# sika_UI.net
KiCad netlist of a schematic drawn in Altium Designer
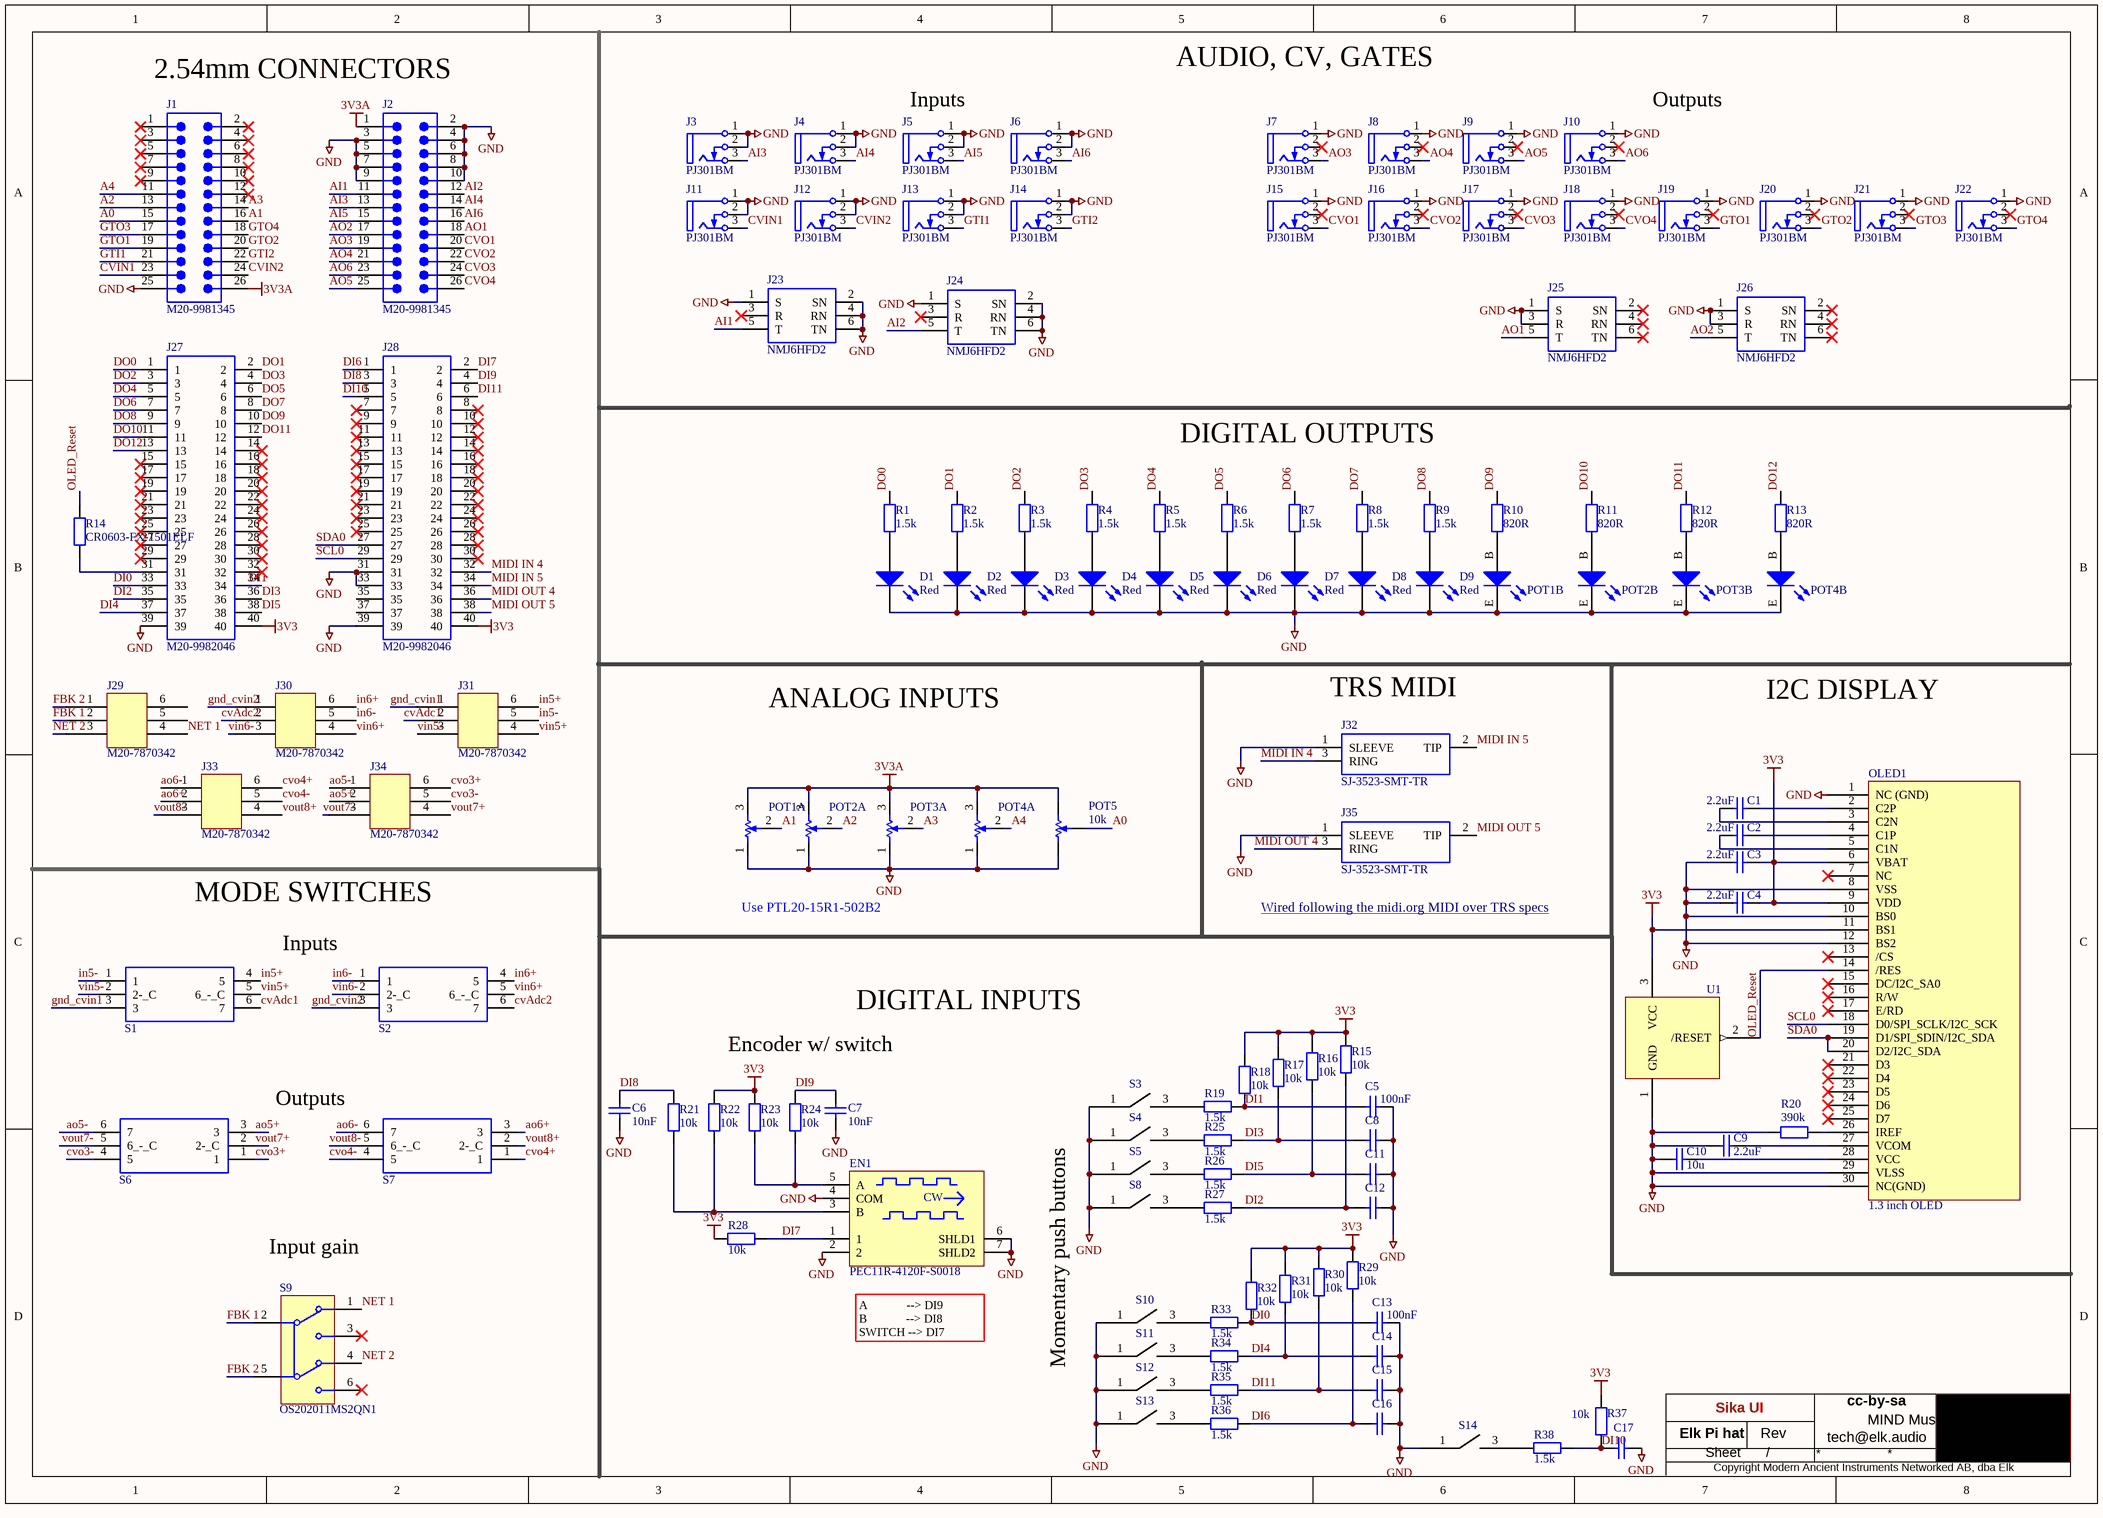
[diagram p0: sika_UI.SchDoc]

(export (version "E")
  (design (tool "Eeschema 10.0.6"))
  (components
    (comp (ref "C1")
      (value "CL10B225KP8NNNC")
      (footprint "C0603")
      (description "Cap Ceramic 10%")
      (fields
        (field (name "MANUFACTURER") "Samsung")
        (field (name "TOLERANCE") "10%")
        (field (name "CAPACITANCE") "2.2uF")
      )
      (libsource (lib "sika_UI") (part "CAP_2U2"))
    )
    (comp (ref "C2")
      (value "CL10B225KP8NNNC")
      (footprint "C0603")
      (description "Cap Ceramic 10%")
      (fields
        (field (name "MANUFACTURER") "Samsung")
        (field (name "TOLERANCE") "10%")
        (field (name "CAPACITANCE") "2.2uF")
      )
      (libsource (lib "sika_UI") (part "CAP_2U2"))
    )
    (comp (ref "C3")
      (value "CL10B225KP8NNNC")
      (footprint "C0603")
      (description "Cap Ceramic 10%")
      (fields
        (field (name "MANUFACTURER") "Samsung")
        (field (name "TOLERANCE") "10%")
        (field (name "CAPACITANCE") "2.2uF")
      )
      (libsource (lib "sika_UI") (part "CAP_2U2"))
    )
    (comp (ref "C4")
      (value "CL10B225KP8NNNC")
      (footprint "C0603")
      (description "Cap Ceramic 10%")
      (fields
        (field (name "MANUFACTURER") "Samsung")
        (field (name "TOLERANCE") "10%")
        (field (name "CAPACITANCE") "2.2uF")
      )
      (libsource (lib "sika_UI") (part "CAP_2U2"))
    )
    (comp (ref "C5")
      (value "CL10B104KO8NNNC")
      (footprint "C0603")
      (description "Cap Ceramic 10%")
      (fields
        (field (name "MANUFACTURER") "Samsung")
        (field (name "MANUFACTURER PART NUMBER") "CL10B105KO8NNNC")
        (field (name "CAPACITANCE") "100nF")
      )
      (libsource (lib "sika_UI") (part "CAP_100N"))
    )
    (comp (ref "C6")
      (value "CL10b103JB8NNNC")
      (footprint "C0603")
      (description "Cap Ceramic 10%")
      (fields
        (field (name "MANUFACTURER") "Samsung")
        (field (name "MANUFACTURER PART NUMBER") "CL10B105KO8NNNC")
        (field (name "CAPACITANCE") "10nF")
      )
      (libsource (lib "sika_UI") (part "CAP_10N"))
    )
    (comp (ref "C7")
      (value "CL10b103JB8NNNC")
      (footprint "C0603")
      (description "Cap Ceramic 10%")
      (fields
        (field (name "MANUFACTURER") "Samsung")
        (field (name "MANUFACTURER PART NUMBER") "CL10B105KO8NNNC")
        (field (name "CAPACITANCE") "10nF")
      )
      (libsource (lib "sika_UI") (part "CAP_10N"))
    )
    (comp (ref "C8")
      (value "CL10B104KO8NNNC")
      (footprint "C0603")
      (description "Cap Ceramic 10%")
      (fields
        (field (name "MANUFACTURER") "Samsung")
        (field (name "MANUFACTURER PART NUMBER") "CL10B105KO8NNNC")
      )
      (libsource (lib "sika_UI") (part "CAP_100N"))
    )
    (comp (ref "C9")
      (value "CL10B225KP8NNNC")
      (footprint "C0603")
      (description "Cap Ceramic 10%")
      (fields
        (field (name "MANUFACTURER") "Samsung")
        (field (name "TOLERANCE") "10%")
        (field (name "CAPACITANCE") "2.2uF")
      )
      (libsource (lib "sika_UI") (part "CAP_2U2"))
    )
    (comp (ref "C10")
      (value "CAP_10U")
      (footprint "C0603")
      (description "Cap Ceramic 10%")
      (fields
        (field (name "MANUFACTURER") "Samsung")
        (field (name "TOLERANCE") "10%")
        (field (name "CAPACITANCE") "10u")
      )
      (libsource (lib "sika_UI") (part "CAP_10U"))
    )
    (comp (ref "C11")
      (value "CL10B104KO8NNNC")
      (footprint "C0603")
      (description "Cap Ceramic 10%")
      (fields
        (field (name "MANUFACTURER") "Samsung")
        (field (name "MANUFACTURER PART NUMBER") "CL10B105KO8NNNC")
      )
      (libsource (lib "sika_UI") (part "CAP_100N"))
    )
    (comp (ref "C12")
      (value "CL10B104KO8NNNC")
      (footprint "C0603")
      (description "Cap Ceramic 10%")
      (fields
        (field (name "MANUFACTURER") "Samsung")
        (field (name "MANUFACTURER PART NUMBER") "CL10B105KO8NNNC")
      )
      (libsource (lib "sika_UI") (part "CAP_100N"))
    )
    (comp (ref "C13")
      (value "CL10B104KO8NNNC")
      (footprint "C0603")
      (description "Cap Ceramic 10%")
      (fields
        (field (name "MANUFACTURER") "Samsung")
        (field (name "MANUFACTURER PART NUMBER") "CL10B105KO8NNNC")
        (field (name "CAPACITANCE") "100nF")
      )
      (libsource (lib "sika_UI") (part "CAP_100N"))
    )
    (comp (ref "C14")
      (value "CL10B104KO8NNNC")
      (footprint "C0603")
      (description "Cap Ceramic 10%")
      (fields
        (field (name "MANUFACTURER") "Samsung")
        (field (name "MANUFACTURER PART NUMBER") "CL10B105KO8NNNC")
      )
      (libsource (lib "sika_UI") (part "CAP_100N"))
    )
    (comp (ref "C15")
      (value "CL10B104KO8NNNC")
      (footprint "C0603")
      (description "Cap Ceramic 10%")
      (fields
        (field (name "MANUFACTURER") "Samsung")
        (field (name "MANUFACTURER PART NUMBER") "CL10B105KO8NNNC")
      )
      (libsource (lib "sika_UI") (part "CAP_100N"))
    )
    (comp (ref "C16")
      (value "CL10B104KO8NNNC")
      (footprint "C0603")
      (description "Cap Ceramic 10%")
      (fields
        (field (name "MANUFACTURER") "Samsung")
        (field (name "MANUFACTURER PART NUMBER") "CL10B105KO8NNNC")
      )
      (libsource (lib "sika_UI") (part "CAP_100N"))
    )
    (comp (ref "C17")
      (value "CL10B104KO8NNNC")
      (footprint "C0603")
      (description "Cap Ceramic 10%")
      (fields
        (field (name "MANUFACTURER") "Samsung")
        (field (name "MANUFACTURER PART NUMBER") "CL10B105KO8NNNC")
      )
      (libsource (lib "sika_UI") (part "CAP_100N"))
    )
    (comp (ref "D1")
      (value "0")
      (footprint "PCB-9pb35s7134wdnkutz46f-1")
      (description "Standard LEDs; SMD 0610 Dome Lens LED; 1.6x0.8 mm; Red; (Cut Reel)")
      (fields (field (name "MANUFACTURER PART NUMBER") "APTD1608LSURCK") (field (name "COLOR") "Red"))
      (libsource (lib "sika_UI") (part "CMP-3990f44d6d24e657-1"))
    )
    (comp (ref "D2")
      (value "0")
      (footprint "PCB-9pb35s7134wdnkutz46f-1")
      (description "Standard LEDs; SMD 0610 Dome Lens LED; 1.6x0.8 mm; Red; (Cut Reel)")
      (fields (field (name "MANUFACTURER PART NUMBER") "APTD1608LSURCK") (field (name "COLOR") "Red"))
      (libsource (lib "sika_UI") (part "CMP-3990f44d6d24e657-1"))
    )
    (comp (ref "D3")
      (value "0")
      (footprint "PCB-9pb35s7134wdnkutz46f-1")
      (description "Standard LEDs; SMD 0610 Dome Lens LED; 1.6x0.8 mm; Red; (Cut Reel)")
      (fields (field (name "MANUFACTURER PART NUMBER") "APTD1608LSURCK") (field (name "COLOR") "Red"))
      (libsource (lib "sika_UI") (part "CMP-3990f44d6d24e657-1"))
    )
    (comp (ref "D4")
      (value "0")
      (footprint "PCB-9pb35s7134wdnkutz46f-1")
      (description "Standard LEDs; SMD 0610 Dome Lens LED; 1.6x0.8 mm; Red; (Cut Reel)")
      (fields (field (name "MANUFACTURER PART NUMBER") "APTD1608LSURCK") (field (name "COLOR") "Red"))
      (libsource (lib "sika_UI") (part "CMP-3990f44d6d24e657-1"))
    )
    (comp (ref "D5")
      (value "0")
      (footprint "PCB-9pb35s7134wdnkutz46f-1")
      (description "Standard LEDs; SMD 0610 Dome Lens LED; 1.6x0.8 mm; Red; (Cut Reel)")
      (fields (field (name "MANUFACTURER PART NUMBER") "APTD1608LSURCK") (field (name "COLOR") "Red"))
      (libsource (lib "sika_UI") (part "CMP-3990f44d6d24e657-1"))
    )
    (comp (ref "D6")
      (value "0")
      (footprint "PCB-9pb35s7134wdnkutz46f-1")
      (description "Standard LEDs; SMD 0610 Dome Lens LED; 1.6x0.8 mm; Red; (Cut Reel)")
      (fields (field (name "MANUFACTURER PART NUMBER") "APTD1608LSURCK") (field (name "COLOR") "Red"))
      (libsource (lib "sika_UI") (part "CMP-3990f44d6d24e657-1"))
    )
    (comp (ref "D7")
      (value "0")
      (footprint "PCB-9pb35s7134wdnkutz46f-1")
      (description "Standard LEDs; SMD 0610 Dome Lens LED; 1.6x0.8 mm; Red; (Cut Reel)")
      (fields (field (name "MANUFACTURER PART NUMBER") "APTD1608LSURCK") (field (name "COLOR") "Red"))
      (libsource (lib "sika_UI") (part "CMP-3990f44d6d24e657-1"))
    )
    (comp (ref "D8")
      (value "0")
      (footprint "PCB-9pb35s7134wdnkutz46f-1")
      (description "Standard LEDs; SMD 0610 Dome Lens LED; 1.6x0.8 mm; Red; (Cut Reel)")
      (fields (field (name "MANUFACTURER PART NUMBER") "APTD1608LSURCK") (field (name "COLOR") "Red"))
      (libsource (lib "sika_UI") (part "CMP-3990f44d6d24e657-1"))
    )
    (comp (ref "D9")
      (value "0")
      (footprint "PCB-9pb35s7134wdnkutz46f-1")
      (description "Standard LEDs; SMD 0610 Dome Lens LED; 1.6x0.8 mm; Red; (Cut Reel)")
      (fields (field (name "MANUFACTURER PART NUMBER") "APTD1608LSURCK") (field (name "COLOR") "Red"))
      (libsource (lib "sika_UI") (part "CMP-3990f44d6d24e657-1"))
    )
    (comp (ref "EN1")
      (value "PEC11R-4120F-S0018")
      (footprint "BOUR-PEC11R-4XXXF-SXXXX_V - Cloned")
      (description "Encoders 20mm SHAFT w/SWITCH")
      (fields (field (name "MANUFACTURER") "Bourns"))
      (libsource (lib "sika_UI") (part "PEC11R-4120F-S0018"))
    )
    (comp (ref "J1")
      (value "M20-9981345")
      (footprint "HEADER_26")
      (description "CONN HEADER 26POS .100 STR 15AU")
      (fields
        (field (name "MANUFACTURER") "Amphenol FCI")
        (field (name "MANUFACTURER PART NUMBER") "67997-226HLF")
      )
      (libsource (lib "sika_UI") (part "HEADER_26"))
    )
    (comp (ref "J2")
      (value "M20-9981345")
      (footprint "HEADER_26")
      (description "CONN HEADER 26POS .100 STR 15AU")
      (fields
        (field (name "MANUFACTURER") "Amphenol FCI")
        (field (name "MANUFACTURER PART NUMBER") "67997-226HLF")
      )
      (libsource (lib "sika_UI") (part "HEADER_26"))
    )
    (comp (ref "J3") (value "PJ301BM") (footprint "PJ301BM") (libsource (lib "sika_UI") (part "PJ301BM")))
    (comp (ref "J4") (value "PJ301BM") (footprint "PJ301BM") (libsource (lib "sika_UI") (part "PJ301BM")))
    (comp (ref "J5") (value "PJ301BM") (footprint "PJ301BM") (libsource (lib "sika_UI") (part "PJ301BM")))
    (comp (ref "J6") (value "PJ301BM") (footprint "PJ301BM") (libsource (lib "sika_UI") (part "PJ301BM")))
    (comp (ref "J7") (value "PJ301BM") (footprint "PJ301BM") (libsource (lib "sika_UI") (part "PJ301BM")))
    (comp (ref "J8") (value "PJ301BM") (footprint "PJ301BM") (libsource (lib "sika_UI") (part "PJ301BM")))
    (comp (ref "J9") (value "PJ301BM") (footprint "PJ301BM") (libsource (lib "sika_UI") (part "PJ301BM")))
    (comp (ref "J10") (value "PJ301BM") (footprint "PJ301BM") (libsource (lib "sika_UI") (part "PJ301BM")))
    (comp (ref "J11") (value "PJ301BM") (footprint "PJ301BM") (libsource (lib "sika_UI") (part "PJ301BM")))
    (comp (ref "J12") (value "PJ301BM") (footprint "PJ301BM") (libsource (lib "sika_UI") (part "PJ301BM")))
    (comp (ref "J13") (value "PJ301BM") (footprint "PJ301BM") (libsource (lib "sika_UI") (part "PJ301BM")))
    (comp (ref "J14") (value "PJ301BM") (footprint "PJ301BM") (libsource (lib "sika_UI") (part "PJ301BM")))
    (comp (ref "J15") (value "PJ301BM") (footprint "PJ301BM") (libsource (lib "sika_UI") (part "PJ301BM")))
    (comp (ref "J16") (value "PJ301BM") (footprint "PJ301BM") (libsource (lib "sika_UI") (part "PJ301BM")))
    (comp (ref "J17") (value "PJ301BM") (footprint "PJ301BM") (libsource (lib "sika_UI") (part "PJ301BM")))
    (comp (ref "J18") (value "PJ301BM") (footprint "PJ301BM") (libsource (lib "sika_UI") (part "PJ301BM")))
    (comp (ref "J19") (value "PJ301BM") (footprint "PJ301BM") (libsource (lib "sika_UI") (part "PJ301BM")))
    (comp (ref "J20") (value "PJ301BM") (footprint "PJ301BM") (libsource (lib "sika_UI") (part "PJ301BM")))
    (comp (ref "J21") (value "PJ301BM") (footprint "PJ301BM") (libsource (lib "sika_UI") (part "PJ301BM")))
    (comp (ref "J22") (value "PJ301BM") (footprint "PJ301BM") (libsource (lib "sika_UI") (part "PJ301BM")))
    (comp (ref "J23")
      (value "NMJ6HFD2")
      (footprint "NMJ6HFD2")
      (description "Phone Connectors 3C STEREO 3-SPST NC")
      (fields (field (name "MOUSER PART NUMBER") "550-20301"))
      (libsource (lib "sika_UI") (part "NMJ6HFD2"))
    )
    (comp (ref "J24")
      (value "NMJ6HFD2")
      (footprint "NMJ6HFD2")
      (description "Phone Connectors 3C STEREO 3-SPST NC")
      (fields (field (name "MOUSER PART NUMBER") "550-20301"))
      (libsource (lib "sika_UI") (part "NMJ6HFD2"))
    )
    (comp (ref "J25")
      (value "NMJ6HFD2")
      (footprint "NMJ6HFD2")
      (description "Phone Connectors 3C STEREO 3-SPST NC")
      (fields (field (name "MOUSER PART NUMBER") "550-20301"))
      (libsource (lib "sika_UI") (part "NMJ6HFD2"))
    )
    (comp (ref "J26")
      (value "NMJ6HFD2")
      (footprint "NMJ6HFD2")
      (description "Phone Connectors 3C STEREO 3-SPST NC")
      (fields (field (name "MOUSER PART NUMBER") "550-20301"))
      (libsource (lib "sika_UI") (part "NMJ6HFD2"))
    )
    (comp (ref "J27")
      (value "M20-9982046")
      (footprint "header2x20")
      (description "Unshrouded, Pitch 2.54 mm, 6.1 mm Mating distance")
      (fields
        (field (name "MANUFACTURER_PART_NUMBER") "4P01-2A02-DA")
        (field (name "RS PART NUMBER") "8277403")
      )
      (libsource (lib "sika_UI") (part "HEADER_2X20"))
    )
    (comp (ref "J28")
      (value "M20-9982046")
      (footprint "header2x20")
      (description "Unshrouded, Pitch 2.54 mm, 6.1 mm Mating distance")
      (fields
        (field (name "MANUFACTURER_PART_NUMBER") "4P01-2A02-DA")
        (field (name "RS PART NUMBER") "8277403")
      )
      (libsource (lib "sika_UI") (part "HEADER_2X20"))
    )
    (comp (ref "J29")
      (value "M20-7870342")
      (footprint "M207870342")
      (fields (field (name "MANUFACTURER") "Harwin"))
      (libsource (lib "sika_UI") (part "M20-7870342"))
    )
    (comp (ref "J30")
      (value "M20-7870342")
      (footprint "M207870342")
      (fields (field (name "MANUFACTURER") "Harwin"))
      (libsource (lib "sika_UI") (part "M20-7870342"))
    )
    (comp (ref "J31")
      (value "M20-7870342")
      (footprint "M207870342")
      (fields (field (name "MANUFACTURER") "Harwin"))
      (libsource (lib "sika_UI") (part "M20-7870342"))
    )
    (comp (ref "J32")
      (value "SJ-3523-SMT-TR")
      (footprint "SJ3523SMTTR")
      (description "CONN JACK STEREO 3.5MM SMD R/A")
      (fields (field (name "MANUFACTURER") "CUI"))
      (libsource (lib "sika_UI") (part "SJ-3523-SMT-TR"))
    )
    (comp (ref "J33")
      (value "M20-7870342")
      (footprint "M207870342")
      (fields (field (name "MANUFACTURER") "Harwin"))
      (libsource (lib "sika_UI") (part "M20-7870342"))
    )
    (comp (ref "J34")
      (value "M20-7870342")
      (footprint "M207870342")
      (fields (field (name "MANUFACTURER") "Harwin"))
      (libsource (lib "sika_UI") (part "M20-7870342"))
    )
    (comp (ref "J35")
      (value "SJ-3523-SMT-TR")
      (footprint "SJ3523SMTTR")
      (description "CONN JACK STEREO 3.5MM SMD R/A")
      (fields (field (name "MANUFACTURER") "CUI"))
      (libsource (lib "sika_UI") (part "SJ-3523-SMT-TR"))
    )
    (comp (ref "OLED1")
      (value "1.3 inch OLED")
      (footprint "1.3 inch OLED")
      (libsource (lib "sika_UI") (part "1.3 inch OLED"))
    )
    (comp (ref "POT1")
      (value "PTL20-15R1")
      (footprint "slide pot 20 mm")
      (libsource (lib "sika_UI") (part "PTL20-15R1"))
    )
    (comp (ref "POT2")
      (value "PTL20-15R1")
      (footprint "slide pot 20 mm")
      (libsource (lib "sika_UI") (part "PTL20-15R1"))
    )
    (comp (ref "POT3")
      (value "PTL20-15R1")
      (footprint "slide pot 20 mm")
      (libsource (lib "sika_UI") (part "PTL20-15R1"))
    )
    (comp (ref "POT4")
      (value "PTL20-15R1")
      (footprint "slide pot 20 mm")
      (libsource (lib "sika_UI") (part "PTL20-15R1"))
    )
    (comp (ref "POT5")
      (value "10k")
      (footprint "trim pot 25mm")
      (description "25 mm tall (thonk)")
      (libsource (lib "sika_UI") (part "trimmer_pot"))
    )
    (comp (ref "R1")
      (value "CR0603-FX-1501ELF")
      (footprint "R0603")
      (description "Resistor, Ceramic")
      (fields (field (name "RESISTANCE") "1.5k"))
      (libsource (lib "sika_UI") (part "RES_1K5"))
    )
    (comp (ref "R2")
      (value "CR0603-FX-1501ELF")
      (footprint "R0603")
      (description "Resistor, Ceramic")
      (fields (field (name "RESISTANCE") "1.5k"))
      (libsource (lib "sika_UI") (part "RES_1K5"))
    )
    (comp (ref "R3")
      (value "CR0603-FX-1501ELF")
      (footprint "R0603")
      (description "Resistor, Ceramic")
      (fields (field (name "RESISTANCE") "1.5k"))
      (libsource (lib "sika_UI") (part "RES_1K5"))
    )
    (comp (ref "R4")
      (value "CR0603-FX-1501ELF")
      (footprint "R0603")
      (description "Resistor, Ceramic")
      (fields (field (name "RESISTANCE") "1.5k"))
      (libsource (lib "sika_UI") (part "RES_1K5"))
    )
    (comp (ref "R5")
      (value "CR0603-FX-1501ELF")
      (footprint "R0603")
      (description "Resistor, Ceramic")
      (fields (field (name "RESISTANCE") "1.5k"))
      (libsource (lib "sika_UI") (part "RES_1K5"))
    )
    (comp (ref "R6")
      (value "CR0603-FX-1501ELF")
      (footprint "R0603")
      (description "Resistor, Ceramic")
      (fields (field (name "RESISTANCE") "1.5k"))
      (libsource (lib "sika_UI") (part "RES_1K5"))
    )
    (comp (ref "R7")
      (value "CR0603-FX-1501ELF")
      (footprint "R0603")
      (description "Resistor, Ceramic")
      (fields (field (name "RESISTANCE") "1.5k"))
      (libsource (lib "sika_UI") (part "RES_1K5"))
    )
    (comp (ref "R8")
      (value "CR0603-FX-1501ELF")
      (footprint "R0603")
      (description "Resistor, Ceramic")
      (fields (field (name "RESISTANCE") "1.5k"))
      (libsource (lib "sika_UI") (part "RES_1K5"))
    )
    (comp (ref "R9")
      (value "CR0603-FX-1501ELF")
      (footprint "R0603")
      (description "Resistor, Ceramic")
      (fields (field (name "RESISTANCE") "1.5k"))
      (libsource (lib "sika_UI") (part "RES_1K5"))
    )
    (comp (ref "R10")
      (value "CR0603-FX-1501ELF")
      (footprint "R0603")
      (description "Resistor, Ceramic")
      (fields (field (name "RESISTANCE") "820R"))
      (libsource (lib "sika_UI") (part "RES_1K5"))
    )
    (comp (ref "R11")
      (value "CR0603-FX-1501ELF")
      (footprint "R0603")
      (description "Resistor, Ceramic")
      (fields (field (name "RESISTANCE") "820R"))
      (libsource (lib "sika_UI") (part "RES_1K5"))
    )
    (comp (ref "R12")
      (value "CR0603-FX-1501ELF")
      (footprint "R0603")
      (description "Resistor, Ceramic")
      (fields (field (name "RESISTANCE") "820R"))
      (libsource (lib "sika_UI") (part "RES_1K5"))
    )
    (comp (ref "R13")
      (value "CR0603-FX-1501ELF")
      (footprint "R0603")
      (description "Resistor, Ceramic")
      (fields (field (name "RESISTANCE") "820R"))
      (libsource (lib "sika_UI") (part "RES_1K5"))
    )
    (comp (ref "R14")
      (value "CR0603-FX-1501ELF")
      (footprint "R0603")
      (description "Resistor, Ceramic")
      (libsource (lib "sika_UI") (part "RES_DNP"))
    )
    (comp (ref "R15")
      (value "CR0603-FX-1002ELF")
      (footprint "R0603")
      (description "Resistor, Ceramic")
      (fields (field (name "RESISTANCE") "10k"))
      (libsource (lib "") (part "RES_10K_2"))
    )
    (comp (ref "R16")
      (value "CR0603-FX-1002ELF")
      (footprint "R0603")
      (description "Resistor, Ceramic")
      (fields (field (name "RESISTANCE") "10k"))
      (libsource (lib "") (part "RES_10K_2"))
    )
    (comp (ref "R17")
      (value "CR0603-FX-1002ELF")
      (footprint "R0603")
      (description "Resistor, Ceramic")
      (fields (field (name "RESISTANCE") "10k"))
      (libsource (lib "") (part "RES_10K_2"))
    )
    (comp (ref "R18")
      (value "CR0603-FX-1002ELF")
      (footprint "R0603")
      (description "Resistor, Ceramic")
      (fields (field (name "RESISTANCE") "10k"))
      (libsource (lib "") (part "RES_10K_2"))
    )
    (comp (ref "R19")
      (value "CR0603-FX-1501ELF")
      (footprint "R0603")
      (description "Resistor, Ceramic")
      (fields (field (name "RESISTANCE") "1.5k"))
      (libsource (lib "") (part "RES_1K5_1"))
    )
    (comp (ref "R20")
      (value "390k")
      (footprint "R0603")
      (description "Resistor, Ceramic")
      (libsource (lib "sika_UI") (part "RES_390K"))
    )
    (comp (ref "R21")
      (value "CR0603-FX-1002ELF")
      (footprint "R0603")
      (description "Resistor, Ceramic")
      (fields (field (name "RESISTANCE") "10k"))
      (libsource (lib "sika_UI") (part "RES_10K"))
    )
    (comp (ref "R22")
      (value "CR0603-FX-1002ELF")
      (footprint "R0603")
      (description "Resistor, Ceramic")
      (fields (field (name "RESISTANCE") "10k"))
      (libsource (lib "") (part "RES_10K_2"))
    )
    (comp (ref "R23")
      (value "CR0603-FX-1002ELF")
      (footprint "R0603")
      (description "Resistor, Ceramic")
      (fields (field (name "RESISTANCE") "10k"))
      (libsource (lib "sika_UI") (part "RES_10K"))
    )
    (comp (ref "R24")
      (value "CR0603-FX-1002ELF")
      (footprint "R0603")
      (description "Resistor, Ceramic")
      (fields (field (name "RESISTANCE") "10k"))
      (libsource (lib "") (part "RES_10K_2"))
    )
    (comp (ref "R25")
      (value "CR0603-FX-1501ELF")
      (footprint "R0603")
      (description "Resistor, Ceramic")
      (fields (field (name "RESISTANCE") "1.5k"))
      (libsource (lib "") (part "RES_1K5_1"))
    )
    (comp (ref "R26")
      (value "CR0603-FX-1501ELF")
      (footprint "R0603")
      (description "Resistor, Ceramic")
      (fields (field (name "RESISTANCE") "1.5k"))
      (libsource (lib "") (part "RES_1K5_1"))
    )
    (comp (ref "R27")
      (value "CR0603-FX-1501ELF")
      (footprint "R0603")
      (description "Resistor, Ceramic")
      (fields (field (name "RESISTANCE") "1.5k"))
      (libsource (lib "") (part "RES_1K5_1"))
    )
    (comp (ref "R28")
      (value "CR0603-FX-1002ELF")
      (footprint "R0603")
      (description "Resistor, Ceramic")
      (fields (field (name "RESISTANCE") "10k"))
      (libsource (lib "") (part "RES_10K_1"))
    )
    (comp (ref "R29")
      (value "CR0603-FX-1002ELF")
      (footprint "R0603")
      (description "Resistor, Ceramic")
      (fields (field (name "RESISTANCE") "10k"))
      (libsource (lib "") (part "RES_10K_2"))
    )
    (comp (ref "R30")
      (value "CR0603-FX-1002ELF")
      (footprint "R0603")
      (description "Resistor, Ceramic")
      (fields (field (name "RESISTANCE") "10k"))
      (libsource (lib "") (part "RES_10K_2"))
    )
    (comp (ref "R31")
      (value "CR0603-FX-1002ELF")
      (footprint "R0603")
      (description "Resistor, Ceramic")
      (fields (field (name "RESISTANCE") "10k"))
      (libsource (lib "") (part "RES_10K_2"))
    )
    (comp (ref "R32")
      (value "CR0603-FX-1002ELF")
      (footprint "R0603")
      (description "Resistor, Ceramic")
      (fields (field (name "RESISTANCE") "10k"))
      (libsource (lib "") (part "RES_10K_2"))
    )
    (comp (ref "R33")
      (value "CR0603-FX-1501ELF")
      (footprint "R0603")
      (description "Resistor, Ceramic")
      (fields (field (name "RESISTANCE") "1.5k"))
      (libsource (lib "") (part "RES_1K5_1"))
    )
    (comp (ref "R34")
      (value "CR0603-FX-1501ELF")
      (footprint "R0603")
      (description "Resistor, Ceramic")
      (fields (field (name "RESISTANCE") "1.5k"))
      (libsource (lib "") (part "RES_1K5_1"))
    )
    (comp (ref "R35")
      (value "CR0603-FX-1501ELF")
      (footprint "R0603")
      (description "Resistor, Ceramic")
      (fields (field (name "RESISTANCE") "1.5k"))
      (libsource (lib "") (part "RES_1K5_1"))
    )
    (comp (ref "R36")
      (value "CR0603-FX-1501ELF")
      (footprint "R0603")
      (description "Resistor, Ceramic")
      (fields (field (name "RESISTANCE") "1.5k"))
      (libsource (lib "") (part "RES_1K5_1"))
    )
    (comp (ref "R37")
      (value "CR0603-FX-1002ELF")
      (footprint "R0603")
      (description "Resistor, Ceramic")
      (fields (field (name "RESISTANCE") "10k"))
      (libsource (lib "") (part "RES_10K_2"))
    )
    (comp (ref "R38")
      (value "CR0603-FX-1501ELF")
      (footprint "R0603")
      (description "Resistor, Ceramic")
      (fields (field (name "RESISTANCE") "1.5k"))
      (libsource (lib "") (part "RES_1K5_1"))
    )
    (comp (ref "S1")
      (value "*JS202011JAQN")
      (footprint "JS202011JAQN")
      (description "SWITCH SMD SLIDE DPDT 300MA 6V")
      (fields
        (field (name "MANUFACTURER") "ITT C&K")
        (field (name "MANUFACTURER PART NUMBER") "JS202011JAQN")
      )
      (libsource (lib "sika_UI") (part "JS202011JAQN"))
    )
    (comp (ref "S2")
      (value "*JS202011JAQN")
      (footprint "JS202011JAQN")
      (description "SWITCH SMD SLIDE DPDT 300MA 6V")
      (fields
        (field (name "MANUFACTURER") "ITT C&K")
        (field (name "MANUFACTURER PART NUMBER") "JS202011JAQN")
      )
      (libsource (lib "sika_UI") (part "JS202011JAQN"))
    )
    (comp (ref "S3")
      (value "Red Tact")
      (footprint "tactile_switch")
      (description "Switch Tactile OFF (ON) SPST Round Button PC Pins 0.05A 24VDC 100000Cycles 2.55N Thru-Hole Loose")
      (fields
        (field (name "MANUFACTURER") "TE Connectivity")
        (field (name "MANUFACTURER PART NUMBER") "1825910-7")
      )
      (libsource (lib "sika_UI") (part "tactile_switch_red"))
    )
    (comp (ref "S4")
      (value "Red Tact")
      (footprint "tactile_switch")
      (description "Switch Tactile OFF (ON) SPST Round Button PC Pins 0.05A 24VDC 100000Cycles 2.55N Thru-Hole Loose")
      (fields
        (field (name "MANUFACTURER") "TE Connectivity")
        (field (name "MANUFACTURER PART NUMBER") "1825910-7")
      )
      (libsource (lib "sika_UI") (part "tactile_switch_red"))
    )
    (comp (ref "S5")
      (value "Red Tact")
      (footprint "tactile_switch")
      (description "Switch Tactile OFF (ON) SPST Round Button PC Pins 0.05A 24VDC 100000Cycles 2.55N Thru-Hole Loose")
      (fields
        (field (name "MANUFACTURER") "TE Connectivity")
        (field (name "MANUFACTURER PART NUMBER") "1825910-7")
      )
      (libsource (lib "sika_UI") (part "tactile_switch_red"))
    )
    (comp (ref "S6")
      (value "*JS202011JAQN")
      (footprint "JS202011JAQN")
      (description "SWITCH SMD SLIDE DPDT 300MA 6V")
      (fields
        (field (name "MANUFACTURER") "ITT C&K")
        (field (name "MANUFACTURER PART NUMBER") "JS202011JAQN")
      )
      (libsource (lib "sika_UI") (part "JS202011JAQN"))
    )
    (comp (ref "S7")
      (value "*JS202011JAQN")
      (footprint "JS202011JAQN")
      (description "SWITCH SMD SLIDE DPDT 300MA 6V")
      (fields
        (field (name "MANUFACTURER") "ITT C&K")
        (field (name "MANUFACTURER PART NUMBER") "JS202011JAQN")
      )
      (libsource (lib "sika_UI") (part "JS202011JAQN"))
    )
    (comp (ref "S8")
      (value "Red Tact")
      (footprint "tactile_switch")
      (description "Switch Tactile OFF (ON) SPST Round Button PC Pins 0.05A 24VDC 100000Cycles 2.55N Thru-Hole Loose")
      (fields
        (field (name "MANUFACTURER") "TE Connectivity")
        (field (name "MANUFACTURER PART NUMBER") "1825910-7")
      )
      (libsource (lib "sika_UI") (part "tactile_switch_red"))
    )
    (comp (ref "S9")
      (value "OS202011MS2QN1")
      (footprint "OS202011MS2QN1")
      (description "SWITCH SLIDE DPDT 100MA 12V")
      (fields (field (name "MANUFACTURER") "ITT C&K"))
      (libsource (lib "sika_UI") (part "OS202011MS2QN1"))
    )
    (comp (ref "S10")
      (value "Red Tact")
      (footprint "tactile_switch")
      (description "Switch Tactile OFF (ON) SPST Round Button PC Pins 0.05A 24VDC 100000Cycles 2.55N Thru-Hole Loose")
      (fields
        (field (name "MANUFACTURER") "TE Connectivity")
        (field (name "MANUFACTURER PART NUMBER") "1825910-7")
      )
      (libsource (lib "sika_UI") (part "tactile_switch_red"))
    )
    (comp (ref "S11")
      (value "Red Tact")
      (footprint "tactile_switch")
      (description "Switch Tactile OFF (ON) SPST Round Button PC Pins 0.05A 24VDC 100000Cycles 2.55N Thru-Hole Loose")
      (fields
        (field (name "MANUFACTURER") "TE Connectivity")
        (field (name "MANUFACTURER PART NUMBER") "1825910-7")
      )
      (libsource (lib "sika_UI") (part "tactile_switch_red"))
    )
    (comp (ref "S12")
      (value "Black Tact")
      (footprint "tactile_switch")
      (description "Switch Tactile OFF (ON) SPST Round Button PC Pins 0.05A 24VDC 100000Cycles 2.55N Thru-Hole Loose")
      (fields
        (field (name "MANUFACTURER") "TE Connectivity")
        (field (name "MANUFACTURER PART NUMBER") "1825910-7")
      )
      (libsource (lib "sika_UI") (part "tactile_switch_red"))
    )
    (comp (ref "S13")
      (value "Red Tact")
      (footprint "tactile_switch")
      (description "Switch Tactile OFF (ON) SPST Round Button PC Pins 0.05A 24VDC 100000Cycles 2.55N Thru-Hole Loose")
      (fields
        (field (name "MANUFACTURER") "TE Connectivity")
        (field (name "MANUFACTURER PART NUMBER") "1825910-7")
      )
      (libsource (lib "sika_UI") (part "tactile_switch_red"))
    )
    (comp (ref "S14")
      (value "1825910-7")
      (footprint "tactile_switch")
      (description "Switch Tactile OFF (ON) SPST Round Button PC Pins 0.05A 24VDC 100000Cycles 2.55N Thru-Hole Loose")
      (fields (field (name "MANUFACTURER") "TE Connectivity"))
      (libsource (lib "sika_UI") (part "tactile_switch_red"))
    )
    (comp (ref "U1")
      (value "reset uC")
      (footprint "SOT95P245X110-3N")
      (description "Reset uC")
      (libsource (lib "sika_UI") (part "APX803-xxSAG-7"))
    )
  )
  (nets
    (net (code "1") (name "/A0") (class "Default")
      (node (ref "J1") (pin "15") (pinfunction "15_15") (pintype "passive"))
      (node (ref "POT5") (pin "P$2") (pinfunction "P$2_P$2") (pintype "passive"))
    )
    (net (code "2") (name "/A1") (class "Default")
      (node (ref "J1") (pin "16") (pinfunction "16_16") (pintype "passive"))
      (node (ref "POT1") (pin "2") (pinfunction "2_2") (pintype "passive"))
    )
    (net (code "3") (name "/A2") (class "Default")
      (node (ref "J1") (pin "13") (pinfunction "13_13") (pintype "passive"))
      (node (ref "POT2") (pin "2") (pinfunction "2_2") (pintype "passive"))
    )
    (net (code "4") (name "/A3") (class "Default")
      (node (ref "J1") (pin "14") (pinfunction "14_14") (pintype "passive"))
      (node (ref "POT3") (pin "2") (pinfunction "2_2") (pintype "passive"))
    )
    (net (code "5") (name "/A4") (class "Default")
      (node (ref "J1") (pin "11") (pinfunction "11_11") (pintype "passive"))
      (node (ref "POT4") (pin "2") (pinfunction "2_2") (pintype "passive"))
    )
    (net (code "6") (name "/AI1") (class "Default")
      (node (ref "J2") (pin "11") (pinfunction "11_11") (pintype "passive"))
      (node (ref "J23") (pin "5") (pinfunction "T_5") (pintype "passive"))
    )
    (net (code "7") (name "/AI2") (class "Default")
      (node (ref "J2") (pin "12") (pinfunction "12_12") (pintype "passive"))
      (node (ref "J24") (pin "5") (pinfunction "T_5") (pintype "passive"))
    )
    (net (code "8") (name "/AI3") (class "Default")
      (node (ref "J2") (pin "13") (pinfunction "13_13") (pintype "passive"))
      (node (ref "J3") (pin "3") (pinfunction "T_3") (pintype "passive"))
    )
    (net (code "9") (name "/AI4") (class "Default")
      (node (ref "J2") (pin "14") (pinfunction "14_14") (pintype "passive"))
      (node (ref "J4") (pin "3") (pinfunction "T_3") (pintype "passive"))
    )
    (net (code "10") (name "/AI5") (class "Default")
      (node (ref "J2") (pin "15") (pinfunction "15_15") (pintype "passive"))
      (node (ref "J5") (pin "3") (pinfunction "T_3") (pintype "passive"))
    )
    (net (code "11") (name "/AI6") (class "Default")
      (node (ref "J2") (pin "16") (pinfunction "16_16") (pintype "passive"))
      (node (ref "J6") (pin "3") (pinfunction "T_3") (pintype "passive"))
    )
    (net (code "12") (name "/AO1") (class "Default")
      (node (ref "J2") (pin "18") (pinfunction "18_18") (pintype "passive"))
      (node (ref "J25") (pin "5") (pinfunction "T_5") (pintype "passive"))
    )
    (net (code "13") (name "/AO2") (class "Default")
      (node (ref "J2") (pin "17") (pinfunction "17_17") (pintype "passive"))
      (node (ref "J26") (pin "5") (pinfunction "T_5") (pintype "passive"))
    )
    (net (code "14") (name "/AO3") (class "Default")
      (node (ref "J2") (pin "19") (pinfunction "19_19") (pintype "passive"))
      (node (ref "J7") (pin "3") (pinfunction "T_3") (pintype "passive"))
    )
    (net (code "15") (name "/AO4") (class "Default")
      (node (ref "J2") (pin "21") (pinfunction "21_21") (pintype "passive"))
      (node (ref "J8") (pin "3") (pinfunction "T_3") (pintype "passive"))
    )
    (net (code "16") (name "/AO5") (class "Default")
      (node (ref "J2") (pin "25") (pinfunction "25_25") (pintype "passive"))
      (node (ref "J9") (pin "3") (pinfunction "T_3") (pintype "passive"))
    )
    (net (code "17") (name "/AO6") (class "Default")
      (node (ref "J10") (pin "3") (pinfunction "T_3") (pintype "passive"))
      (node (ref "J2") (pin "23") (pinfunction "23_23") (pintype "passive"))
    )
    (net (code "18") (name "/CVIN1") (class "Default")
      (node (ref "J1") (pin "23") (pinfunction "23_23") (pintype "passive"))
      (node (ref "J11") (pin "3") (pinfunction "T_3") (pintype "passive"))
    )
    (net (code "19") (name "/CVIN2") (class "Default")
      (node (ref "J1") (pin "24") (pinfunction "24_24") (pintype "passive"))
      (node (ref "J12") (pin "3") (pinfunction "T_3") (pintype "passive"))
    )
    (net (code "20") (name "/CVO1") (class "Default")
      (node (ref "J15") (pin "3") (pinfunction "T_3") (pintype "passive"))
      (node (ref "J2") (pin "20") (pinfunction "20_20") (pintype "passive"))
    )
    (net (code "21") (name "/CVO2") (class "Default")
      (node (ref "J16") (pin "3") (pinfunction "T_3") (pintype "passive"))
      (node (ref "J2") (pin "22") (pinfunction "22_22") (pintype "passive"))
    )
    (net (code "22") (name "/CVO3") (class "Default")
      (node (ref "J17") (pin "3") (pinfunction "T_3") (pintype "passive"))
      (node (ref "J2") (pin "24") (pinfunction "24_24") (pintype "passive"))
    )
    (net (code "23") (name "/CVO4") (class "Default")
      (node (ref "J18") (pin "3") (pinfunction "T_3") (pintype "passive"))
      (node (ref "J2") (pin "26") (pinfunction "26_26") (pintype "passive"))
    )
    (net (code "24") (name "/DI0") (class "Default")
      (node (ref "C13") (pin "1") (pinfunction "1_1") (pintype "passive"))
      (node (ref "J27") (pin "33") (pinfunction "33_33") (pintype "passive"))
      (node (ref "R32") (pin "1") (pinfunction "1_1") (pintype "passive"))
      (node (ref "R33") (pin "1") (pinfunction "1_1") (pintype "passive"))
    )
    (net (code "25") (name "/DI1") (class "Default")
      (node (ref "C5") (pin "1") (pinfunction "1_1") (pintype "passive"))
      (node (ref "J27") (pin "34") (pinfunction "34_34") (pintype "passive"))
      (node (ref "R18") (pin "1") (pinfunction "1_1") (pintype "passive"))
      (node (ref "R19") (pin "1") (pinfunction "1_1") (pintype "passive"))
    )
    (net (code "26") (name "/DI2") (class "Default")
      (node (ref "C12") (pin "1") (pinfunction "1_1") (pintype "passive"))
      (node (ref "J27") (pin "35") (pinfunction "35_35") (pintype "passive"))
      (node (ref "R15") (pin "1") (pinfunction "1_1") (pintype "passive"))
      (node (ref "R27") (pin "1") (pinfunction "1_1") (pintype "passive"))
    )
    (net (code "27") (name "/DI3") (class "Default")
      (node (ref "C8") (pin "1") (pinfunction "1_1") (pintype "passive"))
      (node (ref "J27") (pin "36") (pinfunction "36_36") (pintype "passive"))
      (node (ref "R17") (pin "1") (pinfunction "1_1") (pintype "passive"))
      (node (ref "R25") (pin "1") (pinfunction "1_1") (pintype "passive"))
    )
    (net (code "28") (name "/DI4") (class "Default")
      (node (ref "C14") (pin "1") (pinfunction "1_1") (pintype "passive"))
      (node (ref "J27") (pin "37") (pinfunction "37_37") (pintype "passive"))
      (node (ref "R31") (pin "1") (pinfunction "1_1") (pintype "passive"))
      (node (ref "R34") (pin "1") (pinfunction "1_1") (pintype "passive"))
    )
    (net (code "29") (name "/DI5") (class "Default")
      (node (ref "C11") (pin "1") (pinfunction "1_1") (pintype "passive"))
      (node (ref "J27") (pin "38") (pinfunction "38_38") (pintype "passive"))
      (node (ref "R16") (pin "1") (pinfunction "1_1") (pintype "passive"))
      (node (ref "R26") (pin "1") (pinfunction "1_1") (pintype "passive"))
    )
    (net (code "30") (name "/DI6") (class "Default")
      (node (ref "C16") (pin "1") (pinfunction "1_1") (pintype "passive"))
      (node (ref "J28") (pin "1") (pinfunction "1_1") (pintype "passive"))
      (node (ref "R29") (pin "1") (pinfunction "1_1") (pintype "passive"))
      (node (ref "R36") (pin "1") (pinfunction "1_1") (pintype "passive"))
    )
    (net (code "31") (name "/DI7") (class "Default")
      (node (ref "EN1") (pin "1") (pinfunction "1_1") (pintype "passive"))
      (node (ref "J28") (pin "2") (pinfunction "2_2") (pintype "passive"))
      (node (ref "R28") (pin "1") (pinfunction "1_1") (pintype "passive"))
    )
    (net (code "32") (name "/DI8") (class "Default")
      (node (ref "C6") (pin "2") (pinfunction "2_2") (pintype "passive"))
      (node (ref "J28") (pin "3") (pinfunction "3_3") (pintype "passive"))
      (node (ref "R21") (pin "1") (pinfunction "1_1") (pintype "passive"))
    )
    (net (code "33") (name "/DI9") (class "Default")
      (node (ref "C7") (pin "2") (pinfunction "2_2") (pintype "passive"))
      (node (ref "J28") (pin "4") (pinfunction "4_4") (pintype "passive"))
      (node (ref "R24") (pin "2") (pinfunction "2_2") (pintype "passive"))
    )
    (net (code "34") (name "/DI10") (class "Default")
      (node (ref "C17") (pin "1") (pinfunction "1_1") (pintype "passive"))
      (node (ref "J28") (pin "5") (pinfunction "5_5") (pintype "passive"))
      (node (ref "R37") (pin "1") (pinfunction "1_1") (pintype "passive"))
      (node (ref "R38") (pin "1") (pinfunction "1_1") (pintype "passive"))
    )
    (net (code "35") (name "/DI11") (class "Default")
      (node (ref "C15") (pin "1") (pinfunction "1_1") (pintype "passive"))
      (node (ref "J28") (pin "6") (pinfunction "6_6") (pintype "passive"))
      (node (ref "R30") (pin "1") (pinfunction "1_1") (pintype "passive"))
      (node (ref "R35") (pin "1") (pinfunction "1_1") (pintype "passive"))
    )
    (net (code "36") (name "/DO0") (class "Default")
      (node (ref "J27") (pin "1") (pinfunction "1_1") (pintype "passive"))
      (node (ref "R1") (pin "2") (pinfunction "2_2") (pintype "passive"))
    )
    (net (code "37") (name "/DO1") (class "Default")
      (node (ref "J27") (pin "2") (pinfunction "2_2") (pintype "passive"))
      (node (ref "R2") (pin "2") (pinfunction "2_2") (pintype "passive"))
    )
    (net (code "38") (name "/DO2") (class "Default")
      (node (ref "J27") (pin "3") (pinfunction "3_3") (pintype "passive"))
      (node (ref "R3") (pin "2") (pinfunction "2_2") (pintype "passive"))
    )
    (net (code "39") (name "/DO3") (class "Default")
      (node (ref "J27") (pin "4") (pinfunction "4_4") (pintype "passive"))
      (node (ref "R4") (pin "2") (pinfunction "2_2") (pintype "passive"))
    )
    (net (code "40") (name "/DO4") (class "Default")
      (node (ref "J27") (pin "5") (pinfunction "5_5") (pintype "passive"))
      (node (ref "R5") (pin "2") (pinfunction "2_2") (pintype "passive"))
    )
    (net (code "41") (name "/DO5") (class "Default")
      (node (ref "J27") (pin "6") (pinfunction "6_6") (pintype "passive"))
      (node (ref "R6") (pin "2") (pinfunction "2_2") (pintype "passive"))
    )
    (net (code "42") (name "/DO6") (class "Default")
      (node (ref "J27") (pin "7") (pinfunction "7_7") (pintype "passive"))
      (node (ref "R7") (pin "2") (pinfunction "2_2") (pintype "passive"))
    )
    (net (code "43") (name "/DO7") (class "Default")
      (node (ref "J27") (pin "8") (pinfunction "8_8") (pintype "passive"))
      (node (ref "R8") (pin "2") (pinfunction "2_2") (pintype "passive"))
    )
    (net (code "44") (name "/DO8") (class "Default")
      (node (ref "J27") (pin "9") (pinfunction "9_9") (pintype "passive"))
      (node (ref "R9") (pin "2") (pinfunction "2_2") (pintype "passive"))
    )
    (net (code "45") (name "/DO9") (class "Default")
      (node (ref "J27") (pin "10") (pinfunction "10_10") (pintype "passive"))
      (node (ref "R10") (pin "2") (pinfunction "2_2") (pintype "passive"))
    )
    (net (code "46") (name "/DO10") (class "Default")
      (node (ref "J27") (pin "11") (pinfunction "11_11") (pintype "passive"))
      (node (ref "R11") (pin "2") (pinfunction "2_2") (pintype "passive"))
    )
    (net (code "47") (name "/DO11") (class "Default")
      (node (ref "J27") (pin "12") (pinfunction "12_12") (pintype "passive"))
      (node (ref "R12") (pin "2") (pinfunction "2_2") (pintype "passive"))
    )
    (net (code "48") (name "/DO12") (class "Default")
      (node (ref "J27") (pin "13") (pinfunction "13_13") (pintype "passive"))
      (node (ref "R13") (pin "2") (pinfunction "2_2") (pintype "passive"))
    )
    (net (code "49") (name "/FBK 1") (class "Default")
      (node (ref "J29") (pin "2") (pintype "passive"))
      (node (ref "S9") (pin "2") (pinfunction "2_2") (pintype "passive"))
    )
    (net (code "50") (name "/FBK 2") (class "Default")
      (node (ref "J29") (pin "1") (pintype "passive"))
      (node (ref "S9") (pin "5") (pinfunction "5_5") (pintype "passive"))
    )
    (net (code "51") (name "/GTI1") (class "Default")
      (node (ref "J1") (pin "21") (pinfunction "21_21") (pintype "passive"))
      (node (ref "J13") (pin "3") (pinfunction "T_3") (pintype "passive"))
    )
    (net (code "52") (name "/GTI2") (class "Default")
      (node (ref "J1") (pin "22") (pinfunction "22_22") (pintype "passive"))
      (node (ref "J14") (pin "3") (pinfunction "T_3") (pintype "passive"))
    )
    (net (code "53") (name "/GTO1") (class "Default")
      (node (ref "J1") (pin "19") (pinfunction "19_19") (pintype "passive"))
      (node (ref "J19") (pin "3") (pinfunction "T_3") (pintype "passive"))
    )
    (net (code "54") (name "/GTO2") (class "Default")
      (node (ref "J1") (pin "20") (pinfunction "20_20") (pintype "passive"))
      (node (ref "J20") (pin "3") (pinfunction "T_3") (pintype "passive"))
    )
    (net (code "55") (name "/GTO3") (class "Default")
      (node (ref "J1") (pin "17") (pinfunction "17_17") (pintype "passive"))
      (node (ref "J21") (pin "3") (pinfunction "T_3") (pintype "passive"))
    )
    (net (code "56") (name "/GTO4") (class "Default")
      (node (ref "J1") (pin "18") (pinfunction "18_18") (pintype "passive"))
      (node (ref "J22") (pin "3") (pinfunction "T_3") (pintype "passive"))
    )
    (net (code "57") (name "/MIDI IN 4") (class "Default")
      (node (ref "J28") (pin "32") (pinfunction "32_32") (pintype "passive"))
      (node (ref "J32") (pin "3") (pinfunction "RING_3") (pintype "passive"))
    )
    (net (code "58") (name "/MIDI IN 5") (class "Default")
      (node (ref "J28") (pin "34") (pinfunction "34_34") (pintype "passive"))
      (node (ref "J32") (pin "2") (pinfunction "TIP_2") (pintype "passive"))
    )
    (net (code "59") (name "/MIDI OUT 4") (class "Default")
      (node (ref "J28") (pin "36") (pinfunction "36_36") (pintype "passive"))
      (node (ref "J35") (pin "3") (pinfunction "RING_3") (pintype "passive"))
    )
    (net (code "60") (name "/MIDI OUT 5") (class "Default")
      (node (ref "J28") (pin "38") (pinfunction "38_38") (pintype "passive"))
      (node (ref "J35") (pin "2") (pinfunction "TIP_2") (pintype "passive"))
    )
    (net (code "61") (name "/NET 1") (class "Default")
      (node (ref "J29") (pin "4") (pintype "passive"))
      (node (ref "S9") (pin "1") (pinfunction "1_1") (pintype "passive"))
    )
    (net (code "62") (name "/NET 2") (class "Default")
      (node (ref "J29") (pin "3") (pintype "passive"))
      (node (ref "S9") (pin "4") (pinfunction "4_4") (pintype "passive"))
    )
    (net (code "63") (name "/OLED_Reset") (class "Default")
      (node (ref "OLED1") (pin "14") (pinfunction "/RES_14") (pintype "passive"))
      (node (ref "R14") (pin "2") (pinfunction "2_2") (pintype "passive"))
      (node (ref "U1") (pin "2") (pinfunction "/RESET_2") (pintype "output"))
    )
    (net (code "64") (name "/SCL0") (class "Default")
      (node (ref "J28") (pin "29") (pinfunction "29_29") (pintype "passive"))
      (node (ref "OLED1") (pin "18") (pinfunction "D0/SPI_SCLK/I2C_SCK_18") (pintype "passive"))
    )
    (net (code "65") (name "/SDA0") (class "Default")
      (node (ref "J28") (pin "27") (pinfunction "27_27") (pintype "passive"))
      (node (ref "OLED1") (pin "19") (pinfunction "D1/SPI_SDIN/I2C_SDA_19") (pintype "passive"))
      (node (ref "OLED1") (pin "20") (pinfunction "D2/I2C_SDA_20") (pintype "passive"))
    )
    (net (code "66") (name "/ao5+") (class "Default")
      (node (ref "J34") (pin "2") (pintype "passive"))
      (node (ref "S6") (pin "3") (pinfunction "3_3") (pintype "passive"))
    )
    (net (code "67") (name "/ao5-") (class "Default")
      (node (ref "J34") (pin "1") (pintype "passive"))
      (node (ref "S6") (pin "6") (pinfunction "7_6") (pintype "passive"))
    )
    (net (code "68") (name "/ao6+") (class "Default")
      (node (ref "J33") (pin "2") (pintype "passive"))
      (node (ref "S7") (pin "3") (pinfunction "3_3") (pintype "passive"))
    )
    (net (code "69") (name "/ao6-") (class "Default")
      (node (ref "J33") (pin "1") (pintype "passive"))
      (node (ref "S7") (pin "6") (pinfunction "7_6") (pintype "passive"))
    )
    (net (code "70") (name "/cvAdc1") (class "Default")
      (node (ref "J31") (pin "2") (pintype "passive"))
      (node (ref "S1") (pin "6") (pinfunction "7_6") (pintype "passive"))
    )
    (net (code "71") (name "/cvAdc2") (class "Default")
      (node (ref "J30") (pin "2") (pintype "passive"))
      (node (ref "S2") (pin "6") (pinfunction "7_6") (pintype "passive"))
    )
    (net (code "72") (name "/cvo3+") (class "Default")
      (node (ref "J34") (pin "6") (pintype "passive"))
      (node (ref "S6") (pin "1") (pinfunction "1_1") (pintype "passive"))
    )
    (net (code "73") (name "/cvo3-") (class "Default")
      (node (ref "J34") (pin "5") (pintype "passive"))
      (node (ref "S6") (pin "4") (pinfunction "5_4") (pintype "passive"))
    )
    (net (code "74") (name "/cvo4+") (class "Default")
      (node (ref "J33") (pin "6") (pintype "passive"))
      (node (ref "S7") (pin "1") (pinfunction "1_1") (pintype "passive"))
    )
    (net (code "75") (name "/cvo4-") (class "Default")
      (node (ref "J33") (pin "5") (pintype "passive"))
      (node (ref "S7") (pin "4") (pinfunction "5_4") (pintype "passive"))
    )
    (net (code "76") (name "/gnd_cvin1") (class "Default")
      (node (ref "J31") (pin "1") (pintype "passive"))
      (node (ref "S1") (pin "3") (pinfunction "3_3") (pintype "passive"))
    )
    (net (code "77") (name "/gnd_cvin2") (class "Default")
      (node (ref "J30") (pin "1") (pintype "passive"))
      (node (ref "S2") (pin "3") (pinfunction "3_3") (pintype "passive"))
    )
    (net (code "78") (name "/in5+") (class "Default")
      (node (ref "J31") (pin "6") (pintype "passive"))
      (node (ref "S1") (pin "4") (pinfunction "5_4") (pintype "passive"))
    )
    (net (code "79") (name "/in5-") (class "Default")
      (node (ref "J31") (pin "5") (pintype "passive"))
      (node (ref "S1") (pin "1") (pinfunction "1_1") (pintype "passive"))
    )
    (net (code "80") (name "/in6+") (class "Default")
      (node (ref "J30") (pin "6") (pintype "passive"))
      (node (ref "S2") (pin "4") (pinfunction "5_4") (pintype "passive"))
    )
    (net (code "81") (name "/in6-") (class "Default")
      (node (ref "J30") (pin "5") (pintype "passive"))
      (node (ref "S2") (pin "1") (pinfunction "1_1") (pintype "passive"))
    )
    (net (code "82") (name "/vin5+") (class "Default")
      (node (ref "J31") (pin "4") (pintype "passive"))
      (node (ref "S1") (pin "5") (pinfunction "6_-_C_5") (pintype "passive"))
    )
    (net (code "83") (name "/vin5-") (class "Default")
      (node (ref "J31") (pin "3") (pintype "passive"))
      (node (ref "S1") (pin "2") (pinfunction "2-_C_2") (pintype "passive"))
    )
    (net (code "84") (name "/vin6+") (class "Default")
      (node (ref "J30") (pin "4") (pintype "passive"))
      (node (ref "S2") (pin "5") (pinfunction "6_-_C_5") (pintype "passive"))
    )
    (net (code "85") (name "/vin6-") (class "Default")
      (node (ref "J30") (pin "3") (pintype "passive"))
      (node (ref "S2") (pin "2") (pinfunction "2-_C_2") (pintype "passive"))
    )
    (net (code "86") (name "/vout7+") (class "Default")
      (node (ref "J34") (pin "4") (pintype "passive"))
      (node (ref "S6") (pin "2") (pinfunction "2-_C_2") (pintype "passive"))
    )
    (net (code "87") (name "/vout7-") (class "Default")
      (node (ref "J34") (pin "3") (pintype "passive"))
      (node (ref "S6") (pin "5") (pinfunction "6_-_C_5") (pintype "passive"))
    )
    (net (code "88") (name "/vout8+") (class "Default")
      (node (ref "J33") (pin "4") (pintype "passive"))
      (node (ref "S7") (pin "2") (pinfunction "2-_C_2") (pintype "passive"))
    )
    (net (code "89") (name "/vout8-") (class "Default")
      (node (ref "J33") (pin "3") (pintype "passive"))
      (node (ref "S7") (pin "5") (pinfunction "6_-_C_5") (pintype "passive"))
    )
    (net (code "90") (name "3V3") (class "Default")
      (node (ref "C3") (pin "1") (pinfunction "1_1") (pintype "passive"))
      (node (ref "C4") (pin "1") (pinfunction "1_1") (pintype "passive"))
      (node (ref "J27") (pin "40") (pinfunction "40_40") (pintype "passive"))
      (node (ref "J28") (pin "40") (pinfunction "40_40") (pintype "passive"))
      (node (ref "OLED1") (pin "11") (pinfunction "BS1_11") (pintype "passive"))
      (node (ref "OLED1") (pin "6") (pinfunction "VBAT_6") (pintype "passive"))
      (node (ref "OLED1") (pin "9") (pinfunction "VDD_9") (pintype "passive"))
      (node (ref "R15") (pin "2") (pinfunction "2_2") (pintype "passive"))
      (node (ref "R16") (pin "2") (pinfunction "2_2") (pintype "passive"))
      (node (ref "R17") (pin "2") (pinfunction "2_2") (pintype "passive"))
      (node (ref "R18") (pin "2") (pinfunction "2_2") (pintype "passive"))
      (node (ref "R22") (pin "2") (pinfunction "2_2") (pintype "passive"))
      (node (ref "R23") (pin "1") (pinfunction "1_1") (pintype "passive"))
      (node (ref "R28") (pin "2") (pinfunction "2_2") (pintype "passive"))
      (node (ref "R29") (pin "2") (pinfunction "2_2") (pintype "passive"))
      (node (ref "R30") (pin "2") (pinfunction "2_2") (pintype "passive"))
      (node (ref "R31") (pin "2") (pinfunction "2_2") (pintype "passive"))
      (node (ref "R32") (pin "2") (pinfunction "2_2") (pintype "passive"))
      (node (ref "R37") (pin "2") (pinfunction "2_2") (pintype "passive"))
      (node (ref "U1") (pin "3") (pinfunction "VCC_3") (pintype "power_in"))
    )
    (net (code "91") (name "3V3A") (class "Default")
      (node (ref "J1") (pin "26") (pinfunction "26_26") (pintype "passive"))
      (node (ref "J2") (pin "1") (pinfunction "1_1") (pintype "passive"))
      (node (ref "POT1") (pin "3") (pinfunction "3_3") (pintype "passive"))
      (node (ref "POT2") (pin "3") (pinfunction "3_3") (pintype "passive"))
      (node (ref "POT3") (pin "3") (pinfunction "3_3") (pintype "passive"))
      (node (ref "POT4") (pin "3") (pinfunction "3_3") (pintype "passive"))
      (node (ref "POT5") (pin "P$1") (pinfunction "P$1_P$1") (pintype "passive"))
    )
    (net (code "92") (name "GND") (class "Default")
      (node (ref "C10") (pin "2") (pinfunction "2_2") (pintype "passive"))
      (node (ref "C11") (pin "2") (pinfunction "2_2") (pintype "passive"))
      (node (ref "C12") (pin "2") (pinfunction "2_2") (pintype "passive"))
      (node (ref "C13") (pin "2") (pinfunction "2_2") (pintype "passive"))
      (node (ref "C14") (pin "2") (pinfunction "2_2") (pintype "passive"))
      (node (ref "C15") (pin "2") (pinfunction "2_2") (pintype "passive"))
      (node (ref "C16") (pin "2") (pinfunction "2_2") (pintype "passive"))
      (node (ref "C17") (pin "2") (pinfunction "2_2") (pintype "passive"))
      (node (ref "C3") (pin "2") (pinfunction "2_2") (pintype "passive"))
      (node (ref "C4") (pin "2") (pinfunction "2_2") (pintype "passive"))
      (node (ref "C5") (pin "2") (pinfunction "2_2") (pintype "passive"))
      (node (ref "C6") (pin "1") (pinfunction "1_1") (pintype "passive"))
      (node (ref "C7") (pin "1") (pinfunction "1_1") (pintype "passive"))
      (node (ref "C8") (pin "2") (pinfunction "2_2") (pintype "passive"))
      (node (ref "C9") (pin "2") (pinfunction "2_2") (pintype "passive"))
      (node (ref "D1") (pin "2") (pinfunction "K_2") (pintype "passive"))
      (node (ref "D2") (pin "2") (pinfunction "K_2") (pintype "passive"))
      (node (ref "D3") (pin "2") (pinfunction "K_2") (pintype "passive"))
      (node (ref "D4") (pin "2") (pinfunction "K_2") (pintype "passive"))
      (node (ref "D5") (pin "2") (pinfunction "K_2") (pintype "passive"))
      (node (ref "D6") (pin "2") (pinfunction "K_2") (pintype "passive"))
      (node (ref "D7") (pin "2") (pinfunction "K_2") (pintype "passive"))
      (node (ref "D8") (pin "2") (pinfunction "K_2") (pintype "passive"))
      (node (ref "D9") (pin "2") (pinfunction "K_2") (pintype "passive"))
      (node (ref "EN1") (pin "2") (pinfunction "2_2") (pintype "passive"))
      (node (ref "EN1") (pin "4") (pinfunction "COM_4") (pintype "passive"))
      (node (ref "EN1") (pin "6") (pinfunction "SHLD1_6") (pintype "passive"))
      (node (ref "EN1") (pin "7") (pinfunction "SHLD2_7") (pintype "passive"))
      (node (ref "J1") (pin "25") (pinfunction "25_25") (pintype "passive"))
      (node (ref "J10") (pin "1") (pinfunction "S_1") (pintype "power_in"))
      (node (ref "J11") (pin "1") (pinfunction "S_1") (pintype "power_in"))
      (node (ref "J11") (pin "2") (pinfunction "TN_2") (pintype "passive"))
      (node (ref "J12") (pin "1") (pinfunction "S_1") (pintype "power_in"))
      (node (ref "J12") (pin "2") (pinfunction "TN_2") (pintype "passive"))
      (node (ref "J13") (pin "1") (pinfunction "S_1") (pintype "power_in"))
      (node (ref "J13") (pin "2") (pinfunction "TN_2") (pintype "passive"))
      (node (ref "J14") (pin "1") (pinfunction "S_1") (pintype "power_in"))
      (node (ref "J14") (pin "2") (pinfunction "TN_2") (pintype "passive"))
      (node (ref "J15") (pin "1") (pinfunction "S_1") (pintype "power_in"))
      (node (ref "J16") (pin "1") (pinfunction "S_1") (pintype "power_in"))
      (node (ref "J17") (pin "1") (pinfunction "S_1") (pintype "power_in"))
      (node (ref "J18") (pin "1") (pinfunction "S_1") (pintype "power_in"))
      (node (ref "J19") (pin "1") (pinfunction "S_1") (pintype "power_in"))
      (node (ref "J2") (pin "10") (pinfunction "10_10") (pintype "passive"))
      (node (ref "J2") (pin "2") (pinfunction "2_2") (pintype "passive"))
      (node (ref "J2") (pin "3") (pinfunction "3_3") (pintype "passive"))
      (node (ref "J2") (pin "4") (pinfunction "4_4") (pintype "passive"))
      (node (ref "J2") (pin "5") (pinfunction "5_5") (pintype "passive"))
      (node (ref "J2") (pin "6") (pinfunction "6_6") (pintype "passive"))
      (node (ref "J2") (pin "7") (pinfunction "7_7") (pintype "passive"))
      (node (ref "J2") (pin "8") (pinfunction "8_8") (pintype "passive"))
      (node (ref "J2") (pin "9") (pinfunction "9_9") (pintype "passive"))
      (node (ref "J20") (pin "1") (pinfunction "S_1") (pintype "power_in"))
      (node (ref "J21") (pin "1") (pinfunction "S_1") (pintype "power_in"))
      (node (ref "J22") (pin "1") (pinfunction "S_1") (pintype "power_in"))
      (node (ref "J23") (pin "1") (pinfunction "S_1") (pintype "passive"))
      (node (ref "J23") (pin "2") (pinfunction "SN_2") (pintype "passive"))
      (node (ref "J23") (pin "4") (pinfunction "RN_4") (pintype "passive"))
      (node (ref "J23") (pin "6") (pinfunction "TN_6") (pintype "passive"))
      (node (ref "J24") (pin "1") (pinfunction "S_1") (pintype "passive"))
      (node (ref "J24") (pin "2") (pinfunction "SN_2") (pintype "passive"))
      (node (ref "J24") (pin "4") (pinfunction "RN_4") (pintype "passive"))
      (node (ref "J24") (pin "6") (pinfunction "TN_6") (pintype "passive"))
      (node (ref "J25") (pin "1") (pinfunction "S_1") (pintype "passive"))
      (node (ref "J25") (pin "3") (pinfunction "R_3") (pintype "passive"))
      (node (ref "J26") (pin "1") (pinfunction "S_1") (pintype "passive"))
      (node (ref "J26") (pin "3") (pinfunction "R_3") (pintype "passive"))
      (node (ref "J27") (pin "39") (pinfunction "39_39") (pintype "passive"))
      (node (ref "J28") (pin "31") (pinfunction "31_31") (pintype "passive"))
      (node (ref "J28") (pin "33") (pinfunction "33_33") (pintype "passive"))
      (node (ref "J28") (pin "39") (pinfunction "39_39") (pintype "passive"))
      (node (ref "J3") (pin "1") (pinfunction "S_1") (pintype "power_in"))
      (node (ref "J3") (pin "2") (pinfunction "TN_2") (pintype "passive"))
      (node (ref "J32") (pin "1") (pinfunction "SLEEVE_1") (pintype "passive"))
      (node (ref "J35") (pin "1") (pinfunction "SLEEVE_1") (pintype "passive"))
      (node (ref "J4") (pin "1") (pinfunction "S_1") (pintype "power_in"))
      (node (ref "J4") (pin "2") (pinfunction "TN_2") (pintype "passive"))
      (node (ref "J5") (pin "1") (pinfunction "S_1") (pintype "power_in"))
      (node (ref "J5") (pin "2") (pinfunction "TN_2") (pintype "passive"))
      (node (ref "J6") (pin "1") (pinfunction "S_1") (pintype "power_in"))
      (node (ref "J6") (pin "2") (pinfunction "TN_2") (pintype "passive"))
      (node (ref "J7") (pin "1") (pinfunction "S_1") (pintype "power_in"))
      (node (ref "J8") (pin "1") (pinfunction "S_1") (pintype "power_in"))
      (node (ref "J9") (pin "1") (pinfunction "S_1") (pintype "power_in"))
      (node (ref "OLED1") (pin "1") (pinfunction "NC_(GND)_1") (pintype "passive"))
      (node (ref "OLED1") (pin "10") (pinfunction "BS0_10") (pintype "passive"))
      (node (ref "OLED1") (pin "12") (pinfunction "BS2_12") (pintype "passive"))
      (node (ref "OLED1") (pin "29") (pinfunction "VLSS_29") (pintype "passive"))
      (node (ref "OLED1") (pin "30") (pinfunction "NC(GND)_30") (pintype "passive"))
      (node (ref "OLED1") (pin "8") (pinfunction "VSS_8") (pintype "passive"))
      (node (ref "POT1") (pin "1") (pinfunction "1_1") (pintype "passive"))
      (node (ref "POT1") (pin "E") (pinfunction "E_E") (pintype "passive"))
      (node (ref "POT2") (pin "1") (pinfunction "1_1") (pintype "passive"))
      (node (ref "POT2") (pin "E") (pinfunction "E_E") (pintype "passive"))
      (node (ref "POT3") (pin "1") (pinfunction "1_1") (pintype "passive"))
      (node (ref "POT3") (pin "E") (pinfunction "E_E") (pintype "passive"))
      (node (ref "POT4") (pin "1") (pinfunction "1_1") (pintype "passive"))
      (node (ref "POT4") (pin "E") (pinfunction "E_E") (pintype "passive"))
      (node (ref "POT5") (pin "P$3") (pinfunction "P$3_P$3") (pintype "passive"))
      (node (ref "R20") (pin "1") (pinfunction "1_1") (pintype "passive"))
      (node (ref "S10") (pin "1") (pinfunction "1_1") (pintype "passive"))
      (node (ref "S11") (pin "1") (pinfunction "1_1") (pintype "passive"))
      (node (ref "S12") (pin "1") (pinfunction "1_1") (pintype "passive"))
      (node (ref "S13") (pin "1") (pinfunction "1_1") (pintype "passive"))
      (node (ref "S14") (pin "1") (pinfunction "1_1") (pintype "passive"))
      (node (ref "S3") (pin "1") (pinfunction "1_1") (pintype "passive"))
      (node (ref "S4") (pin "1") (pinfunction "1_1") (pintype "passive"))
      (node (ref "S5") (pin "1") (pinfunction "1_1") (pintype "passive"))
      (node (ref "S8") (pin "1") (pinfunction "1_1") (pintype "passive"))
      (node (ref "U1") (pin "1") (pinfunction "GND_1") (pintype "power_in"))
    )
    (net (code "93") (name "Net-(D1-A)") (class "Default")
      (node (ref "D1") (pin "1") (pinfunction "A_1") (pintype "passive"))
      (node (ref "R1") (pin "1") (pinfunction "1_1") (pintype "passive"))
    )
    (net (code "94") (name "Net-(D2-A)") (class "Default")
      (node (ref "D2") (pin "1") (pinfunction "A_1") (pintype "passive"))
      (node (ref "R2") (pin "1") (pinfunction "1_1") (pintype "passive"))
    )
    (net (code "95") (name "Net-(D3-A)") (class "Default")
      (node (ref "D3") (pin "1") (pinfunction "A_1") (pintype "passive"))
      (node (ref "R3") (pin "1") (pinfunction "1_1") (pintype "passive"))
    )
    (net (code "96") (name "Net-(D4-A)") (class "Default")
      (node (ref "D4") (pin "1") (pinfunction "A_1") (pintype "passive"))
      (node (ref "R4") (pin "1") (pinfunction "1_1") (pintype "passive"))
    )
    (net (code "97") (name "Net-(D5-A)") (class "Default")
      (node (ref "D5") (pin "1") (pinfunction "A_1") (pintype "passive"))
      (node (ref "R5") (pin "1") (pinfunction "1_1") (pintype "passive"))
    )
    (net (code "98") (name "Net-(D6-A)") (class "Default")
      (node (ref "D6") (pin "1") (pinfunction "A_1") (pintype "passive"))
      (node (ref "R6") (pin "1") (pinfunction "1_1") (pintype "passive"))
    )
    (net (code "99") (name "Net-(D7-A)") (class "Default")
      (node (ref "D7") (pin "1") (pinfunction "A_1") (pintype "passive"))
      (node (ref "R7") (pin "1") (pinfunction "1_1") (pintype "passive"))
    )
    (net (code "100") (name "Net-(D8-A)") (class "Default")
      (node (ref "D8") (pin "1") (pinfunction "A_1") (pintype "passive"))
      (node (ref "R8") (pin "1") (pinfunction "1_1") (pintype "passive"))
    )
    (net (code "101") (name "Net-(D9-A)") (class "Default")
      (node (ref "D9") (pin "1") (pinfunction "A_1") (pintype "passive"))
      (node (ref "R9") (pin "1") (pinfunction "1_1") (pintype "passive"))
    )
    (net (code "102") (name "Net-(EN1-A)") (class "Default")
      (node (ref "EN1") (pin "5") (pinfunction "A_5") (pintype "passive"))
      (node (ref "R23") (pin "2") (pinfunction "2_2") (pintype "passive"))
      (node (ref "R24") (pin "1") (pinfunction "1_1") (pintype "passive"))
    )
    (net (code "103") (name "Net-(EN1-B)") (class "Default")
      (node (ref "EN1") (pin "3") (pinfunction "B_3") (pintype "passive"))
      (node (ref "R21") (pin "2") (pinfunction "2_2") (pintype "passive"))
      (node (ref "R22") (pin "1") (pinfunction "1_1") (pintype "passive"))
    )
    (net (code "104") (name "Net-(J27-Pad31)") (class "Default")
      (node (ref "J27") (pin "31") (pinfunction "31_31") (pintype "passive"))
      (node (ref "R14") (pin "1") (pinfunction "1_1") (pintype "passive"))
    )
    (net (code "105") (name "Net-(OLED1-C1N)") (class "Default")
      (node (ref "C2") (pin "2") (pinfunction "2_2") (pintype "passive"))
      (node (ref "OLED1") (pin "5") (pinfunction "C1N_5") (pintype "passive"))
    )
    (net (code "106") (name "Net-(OLED1-C1P)") (class "Default")
      (node (ref "C2") (pin "1") (pinfunction "1_1") (pintype "passive"))
      (node (ref "OLED1") (pin "4") (pinfunction "C1P_4") (pintype "passive"))
    )
    (net (code "107") (name "Net-(OLED1-C2N)") (class "Default")
      (node (ref "C1") (pin "2") (pinfunction "2_2") (pintype "passive"))
      (node (ref "OLED1") (pin "3") (pinfunction "C2N_3") (pintype "passive"))
    )
    (net (code "108") (name "Net-(OLED1-C2P)") (class "Default")
      (node (ref "C1") (pin "1") (pinfunction "1_1") (pintype "passive"))
      (node (ref "OLED1") (pin "2") (pinfunction "C2P_2") (pintype "passive"))
    )
    (net (code "109") (name "Net-(OLED1-IREF)") (class "Default")
      (node (ref "OLED1") (pin "26") (pinfunction "IREF_26") (pintype "passive"))
      (node (ref "R20") (pin "2") (pinfunction "2_2") (pintype "passive"))
    )
    (net (code "110") (name "Net-(OLED1-VCC)") (class "Default")
      (node (ref "C10") (pin "1") (pinfunction "1_1") (pintype "passive"))
      (node (ref "OLED1") (pin "28") (pinfunction "VCC_28") (pintype "passive"))
    )
    (net (code "111") (name "Net-(OLED1-VCOM)") (class "Default")
      (node (ref "C9") (pin "1") (pinfunction "1_1") (pintype "passive"))
      (node (ref "OLED1") (pin "27") (pinfunction "VCOM_27") (pintype "passive"))
    )
    (net (code "112") (name "Net-(POT1-PadB)") (class "Default")
      (node (ref "POT1") (pin "B") (pinfunction "B_B") (pintype "passive"))
      (node (ref "R10") (pin "1") (pinfunction "1_1") (pintype "passive"))
    )
    (net (code "113") (name "Net-(POT2-PadB)") (class "Default")
      (node (ref "POT2") (pin "B") (pinfunction "B_B") (pintype "passive"))
      (node (ref "R11") (pin "1") (pinfunction "1_1") (pintype "passive"))
    )
    (net (code "114") (name "Net-(POT3-PadB)") (class "Default")
      (node (ref "POT3") (pin "B") (pinfunction "B_B") (pintype "passive"))
      (node (ref "R12") (pin "1") (pinfunction "1_1") (pintype "passive"))
    )
    (net (code "115") (name "Net-(POT4-PadB)") (class "Default")
      (node (ref "POT4") (pin "B") (pinfunction "B_B") (pintype "passive"))
      (node (ref "R13") (pin "1") (pinfunction "1_1") (pintype "passive"))
    )
    (net (code "116") (name "Net-(R19-Pad2)") (class "Default")
      (node (ref "R19") (pin "2") (pinfunction "2_2") (pintype "passive"))
      (node (ref "S3") (pin "3") (pinfunction "3_3") (pintype "passive"))
    )
    (net (code "117") (name "Net-(R25-Pad2)") (class "Default")
      (node (ref "R25") (pin "2") (pinfunction "2_2") (pintype "passive"))
      (node (ref "S4") (pin "3") (pinfunction "3_3") (pintype "passive"))
    )
    (net (code "118") (name "Net-(R26-Pad2)") (class "Default")
      (node (ref "R26") (pin "2") (pinfunction "2_2") (pintype "passive"))
      (node (ref "S5") (pin "3") (pinfunction "3_3") (pintype "passive"))
    )
    (net (code "119") (name "Net-(R27-Pad2)") (class "Default")
      (node (ref "R27") (pin "2") (pinfunction "2_2") (pintype "passive"))
      (node (ref "S8") (pin "3") (pinfunction "3_3") (pintype "passive"))
    )
    (net (code "120") (name "Net-(R33-Pad2)") (class "Default")
      (node (ref "R33") (pin "2") (pinfunction "2_2") (pintype "passive"))
      (node (ref "S10") (pin "3") (pinfunction "3_3") (pintype "passive"))
    )
    (net (code "121") (name "Net-(R34-Pad2)") (class "Default")
      (node (ref "R34") (pin "2") (pinfunction "2_2") (pintype "passive"))
      (node (ref "S11") (pin "3") (pinfunction "3_3") (pintype "passive"))
    )
    (net (code "122") (name "Net-(R35-Pad2)") (class "Default")
      (node (ref "R35") (pin "2") (pinfunction "2_2") (pintype "passive"))
      (node (ref "S12") (pin "3") (pinfunction "3_3") (pintype "passive"))
    )
    (net (code "123") (name "Net-(R36-Pad2)") (class "Default")
      (node (ref "R36") (pin "2") (pinfunction "2_2") (pintype "passive"))
      (node (ref "S13") (pin "3") (pinfunction "3_3") (pintype "passive"))
    )
    (net (code "124") (name "Net-(R38-Pad2)") (class "Default")
      (node (ref "R38") (pin "2") (pinfunction "2_2") (pintype "passive"))
      (node (ref "S14") (pin "3") (pinfunction "3_3") (pintype "passive"))
    )
    (net (code "125") (name "unconnected-(J1-Pad1)") (class "Default")
      (node (ref "J1") (pin "1") (pinfunction "1_1") (pintype "passive+no_connect"))
    )
    (net (code "126") (name "unconnected-(J1-Pad2)") (class "Default")
      (node (ref "J1") (pin "2") (pinfunction "2_2") (pintype "passive+no_connect"))
    )
    (net (code "127") (name "unconnected-(J1-Pad3)") (class "Default")
      (node (ref "J1") (pin "3") (pinfunction "3_3") (pintype "passive+no_connect"))
    )
    (net (code "128") (name "unconnected-(J1-Pad4)") (class "Default")
      (node (ref "J1") (pin "4") (pinfunction "4_4") (pintype "passive+no_connect"))
    )
    (net (code "129") (name "unconnected-(J1-Pad5)") (class "Default")
      (node (ref "J1") (pin "5") (pinfunction "5_5") (pintype "passive+no_connect"))
    )
    (net (code "130") (name "unconnected-(J1-Pad6)") (class "Default")
      (node (ref "J1") (pin "6") (pinfunction "6_6") (pintype "passive+no_connect"))
    )
    (net (code "131") (name "unconnected-(J1-Pad7)") (class "Default")
      (node (ref "J1") (pin "7") (pinfunction "7_7") (pintype "passive+no_connect"))
    )
    (net (code "132") (name "unconnected-(J1-Pad8)") (class "Default")
      (node (ref "J1") (pin "8") (pinfunction "8_8") (pintype "passive+no_connect"))
    )
    (net (code "133") (name "unconnected-(J1-Pad9)") (class "Default")
      (node (ref "J1") (pin "9") (pinfunction "9_9") (pintype "passive+no_connect"))
    )
    (net (code "134") (name "unconnected-(J1-Pad10)") (class "Default")
      (node (ref "J1") (pin "10") (pinfunction "10_10") (pintype "passive+no_connect"))
    )
    (net (code "135") (name "unconnected-(J1-Pad12)") (class "Default")
      (node (ref "J1") (pin "12") (pinfunction "12_12") (pintype "passive+no_connect"))
    )
    (net (code "136") (name "unconnected-(J7-TN-Pad2)") (class "Default")
      (node (ref "J7") (pin "2") (pinfunction "TN_2") (pintype "passive+no_connect"))
    )
    (net (code "137") (name "unconnected-(J8-TN-Pad2)") (class "Default")
      (node (ref "J8") (pin "2") (pinfunction "TN_2") (pintype "passive+no_connect"))
    )
    (net (code "138") (name "unconnected-(J9-TN-Pad2)") (class "Default")
      (node (ref "J9") (pin "2") (pinfunction "TN_2") (pintype "passive+no_connect"))
    )
    (net (code "139") (name "unconnected-(J10-TN-Pad2)") (class "Default")
      (node (ref "J10") (pin "2") (pinfunction "TN_2") (pintype "passive+no_connect"))
    )
    (net (code "140") (name "unconnected-(J15-TN-Pad2)") (class "Default")
      (node (ref "J15") (pin "2") (pinfunction "TN_2") (pintype "passive+no_connect"))
    )
    (net (code "141") (name "unconnected-(J16-TN-Pad2)") (class "Default")
      (node (ref "J16") (pin "2") (pinfunction "TN_2") (pintype "passive+no_connect"))
    )
    (net (code "142") (name "unconnected-(J17-TN-Pad2)") (class "Default")
      (node (ref "J17") (pin "2") (pinfunction "TN_2") (pintype "passive+no_connect"))
    )
    (net (code "143") (name "unconnected-(J18-TN-Pad2)") (class "Default")
      (node (ref "J18") (pin "2") (pinfunction "TN_2") (pintype "passive+no_connect"))
    )
    (net (code "144") (name "unconnected-(J19-TN-Pad2)") (class "Default")
      (node (ref "J19") (pin "2") (pinfunction "TN_2") (pintype "passive+no_connect"))
    )
    (net (code "145") (name "unconnected-(J20-TN-Pad2)") (class "Default")
      (node (ref "J20") (pin "2") (pinfunction "TN_2") (pintype "passive+no_connect"))
    )
    (net (code "146") (name "unconnected-(J21-TN-Pad2)") (class "Default")
      (node (ref "J21") (pin "2") (pinfunction "TN_2") (pintype "passive+no_connect"))
    )
    (net (code "147") (name "unconnected-(J22-TN-Pad2)") (class "Default")
      (node (ref "J22") (pin "2") (pinfunction "TN_2") (pintype "passive+no_connect"))
    )
    (net (code "148") (name "unconnected-(J23-R-Pad3)") (class "Default")
      (node (ref "J23") (pin "3") (pinfunction "R_3") (pintype "passive+no_connect"))
    )
    (net (code "149") (name "unconnected-(J24-R-Pad3)") (class "Default")
      (node (ref "J24") (pin "3") (pinfunction "R_3") (pintype "passive+no_connect"))
    )
    (net (code "150") (name "unconnected-(J25-RN-Pad4)") (class "Default")
      (node (ref "J25") (pin "4") (pinfunction "RN_4") (pintype "passive+no_connect"))
    )
    (net (code "151") (name "unconnected-(J25-SN-Pad2)") (class "Default")
      (node (ref "J25") (pin "2") (pinfunction "SN_2") (pintype "passive+no_connect"))
    )
    (net (code "152") (name "unconnected-(J25-TN-Pad6)") (class "Default")
      (node (ref "J25") (pin "6") (pinfunction "TN_6") (pintype "passive+no_connect"))
    )
    (net (code "153") (name "unconnected-(J26-RN-Pad4)") (class "Default")
      (node (ref "J26") (pin "4") (pinfunction "RN_4") (pintype "passive+no_connect"))
    )
    (net (code "154") (name "unconnected-(J26-SN-Pad2)") (class "Default")
      (node (ref "J26") (pin "2") (pinfunction "SN_2") (pintype "passive+no_connect"))
    )
    (net (code "155") (name "unconnected-(J26-TN-Pad6)") (class "Default")
      (node (ref "J26") (pin "6") (pinfunction "TN_6") (pintype "passive+no_connect"))
    )
    (net (code "156") (name "unconnected-(J27-Pad14)") (class "Default")
      (node (ref "J27") (pin "14") (pinfunction "14_14") (pintype "passive+no_connect"))
    )
    (net (code "157") (name "unconnected-(J27-Pad15)") (class "Default")
      (node (ref "J27") (pin "15") (pinfunction "15_15") (pintype "passive+no_connect"))
    )
    (net (code "158") (name "unconnected-(J27-Pad16)") (class "Default")
      (node (ref "J27") (pin "16") (pinfunction "16_16") (pintype "passive+no_connect"))
    )
    (net (code "159") (name "unconnected-(J27-Pad17)") (class "Default")
      (node (ref "J27") (pin "17") (pinfunction "17_17") (pintype "passive+no_connect"))
    )
    (net (code "160") (name "unconnected-(J27-Pad18)") (class "Default")
      (node (ref "J27") (pin "18") (pinfunction "18_18") (pintype "passive+no_connect"))
    )
    (net (code "161") (name "unconnected-(J27-Pad19)") (class "Default")
      (node (ref "J27") (pin "19") (pinfunction "19_19") (pintype "passive+no_connect"))
    )
    (net (code "162") (name "unconnected-(J27-Pad20)") (class "Default")
      (node (ref "J27") (pin "20") (pinfunction "20_20") (pintype "passive+no_connect"))
    )
    (net (code "163") (name "unconnected-(J27-Pad21)") (class "Default")
      (node (ref "J27") (pin "21") (pinfunction "21_21") (pintype "passive+no_connect"))
    )
    (net (code "164") (name "unconnected-(J27-Pad22)") (class "Default")
      (node (ref "J27") (pin "22") (pinfunction "22_22") (pintype "passive+no_connect"))
    )
    (net (code "165") (name "unconnected-(J27-Pad23)") (class "Default")
      (node (ref "J27") (pin "23") (pinfunction "23_23") (pintype "passive+no_connect"))
    )
    (net (code "166") (name "unconnected-(J27-Pad24)") (class "Default")
      (node (ref "J27") (pin "24") (pinfunction "24_24") (pintype "passive+no_connect"))
    )
    (net (code "167") (name "unconnected-(J27-Pad25)") (class "Default")
      (node (ref "J27") (pin "25") (pinfunction "25_25") (pintype "passive+no_connect"))
    )
    (net (code "168") (name "unconnected-(J27-Pad26)") (class "Default")
      (node (ref "J27") (pin "26") (pinfunction "26_26") (pintype "passive+no_connect"))
    )
    (net (code "169") (name "unconnected-(J27-Pad27)") (class "Default")
      (node (ref "J27") (pin "27") (pinfunction "27_27") (pintype "passive+no_connect"))
    )
    (net (code "170") (name "unconnected-(J27-Pad28)") (class "Default")
      (node (ref "J27") (pin "28") (pinfunction "28_28") (pintype "passive+no_connect"))
    )
    (net (code "171") (name "unconnected-(J27-Pad29)") (class "Default")
      (node (ref "J27") (pin "29") (pinfunction "29_29") (pintype "passive+no_connect"))
    )
    (net (code "172") (name "unconnected-(J27-Pad30)") (class "Default")
      (node (ref "J27") (pin "30") (pinfunction "30_30") (pintype "passive+no_connect"))
    )
    (net (code "173") (name "unconnected-(J27-Pad32)") (class "Default")
      (node (ref "J27") (pin "32") (pinfunction "32_32") (pintype "passive+no_connect"))
    )
    (net (code "174") (name "unconnected-(J28-Pad7)") (class "Default")
      (node (ref "J28") (pin "7") (pinfunction "7_7") (pintype "passive+no_connect"))
    )
    (net (code "175") (name "unconnected-(J28-Pad8)") (class "Default")
      (node (ref "J28") (pin "8") (pinfunction "8_8") (pintype "passive+no_connect"))
    )
    (net (code "176") (name "unconnected-(J28-Pad9)") (class "Default")
      (node (ref "J28") (pin "9") (pinfunction "9_9") (pintype "passive+no_connect"))
    )
    (net (code "177") (name "unconnected-(J28-Pad10)") (class "Default")
      (node (ref "J28") (pin "10") (pinfunction "10_10") (pintype "passive+no_connect"))
    )
    (net (code "178") (name "unconnected-(J28-Pad11)") (class "Default")
      (node (ref "J28") (pin "11") (pinfunction "11_11") (pintype "passive+no_connect"))
    )
    (net (code "179") (name "unconnected-(J28-Pad12)") (class "Default")
      (node (ref "J28") (pin "12") (pinfunction "12_12") (pintype "passive+no_connect"))
    )
    (net (code "180") (name "unconnected-(J28-Pad13)") (class "Default")
      (node (ref "J28") (pin "13") (pinfunction "13_13") (pintype "passive+no_connect"))
    )
    (net (code "181") (name "unconnected-(J28-Pad14)") (class "Default")
      (node (ref "J28") (pin "14") (pinfunction "14_14") (pintype "passive+no_connect"))
    )
    (net (code "182") (name "unconnected-(J28-Pad15)") (class "Default")
      (node (ref "J28") (pin "15") (pinfunction "15_15") (pintype "passive+no_connect"))
    )
    (net (code "183") (name "unconnected-(J28-Pad16)") (class "Default")
      (node (ref "J28") (pin "16") (pinfunction "16_16") (pintype "passive+no_connect"))
    )
    (net (code "184") (name "unconnected-(J28-Pad17)") (class "Default")
      (node (ref "J28") (pin "17") (pinfunction "17_17") (pintype "passive+no_connect"))
    )
    (net (code "185") (name "unconnected-(J28-Pad18)") (class "Default")
      (node (ref "J28") (pin "18") (pinfunction "18_18") (pintype "passive+no_connect"))
    )
    (net (code "186") (name "unconnected-(J28-Pad19)") (class "Default")
      (node (ref "J28") (pin "19") (pinfunction "19_19") (pintype "passive+no_connect"))
    )
    (net (code "187") (name "unconnected-(J28-Pad20)") (class "Default")
      (node (ref "J28") (pin "20") (pinfunction "20_20") (pintype "passive+no_connect"))
    )
    (net (code "188") (name "unconnected-(J28-Pad21)") (class "Default")
      (node (ref "J28") (pin "21") (pinfunction "21_21") (pintype "passive+no_connect"))
    )
    (net (code "189") (name "unconnected-(J28-Pad22)") (class "Default")
      (node (ref "J28") (pin "22") (pinfunction "22_22") (pintype "passive+no_connect"))
    )
    (net (code "190") (name "unconnected-(J28-Pad23)") (class "Default")
      (node (ref "J28") (pin "23") (pinfunction "23_23") (pintype "passive+no_connect"))
    )
    (net (code "191") (name "unconnected-(J28-Pad24)") (class "Default")
      (node (ref "J28") (pin "24") (pinfunction "24_24") (pintype "passive+no_connect"))
    )
    (net (code "192") (name "unconnected-(J28-Pad25)") (class "Default")
      (node (ref "J28") (pin "25") (pinfunction "25_25") (pintype "passive+no_connect"))
    )
    (net (code "193") (name "unconnected-(J28-Pad26)") (class "Default")
      (node (ref "J28") (pin "26") (pinfunction "26_26") (pintype "passive+no_connect"))
    )
    (net (code "194") (name "unconnected-(J28-Pad28)") (class "Default")
      (node (ref "J28") (pin "28") (pinfunction "28_28") (pintype "passive+no_connect"))
    )
    (net (code "195") (name "unconnected-(J28-Pad30)") (class "Default")
      (node (ref "J28") (pin "30") (pinfunction "30_30") (pintype "passive+no_connect"))
    )
    (net (code "196") (name "unconnected-(J28-Pad35)") (class "Default")
      (node (ref "J28") (pin "35") (pinfunction "35_35") (pintype "passive"))
    )
    (net (code "197") (name "unconnected-(J28-Pad37)") (class "Default")
      (node (ref "J28") (pin "37") (pinfunction "37_37") (pintype "passive"))
    )
    (net (code "198") (name "unconnected-(J29-Pad5)") (class "Default")
      (node (ref "J29") (pin "5") (pintype "passive"))
    )
    (net (code "199") (name "unconnected-(J29-Pad6)") (class "Default")
      (node (ref "J29") (pin "6") (pintype "passive"))
    )
    (net (code "200") (name "unconnected-(OLED1-D3-Pad21)") (class "Default")
      (node (ref "OLED1") (pin "21") (pinfunction "D3_21") (pintype "passive+no_connect"))
    )
    (net (code "201") (name "unconnected-(OLED1-D4-Pad22)") (class "Default")
      (node (ref "OLED1") (pin "22") (pinfunction "D4_22") (pintype "passive+no_connect"))
    )
    (net (code "202") (name "unconnected-(OLED1-D5-Pad23)") (class "Default")
      (node (ref "OLED1") (pin "23") (pinfunction "D5_23") (pintype "passive+no_connect"))
    )
    (net (code "203") (name "unconnected-(OLED1-D6-Pad24)") (class "Default")
      (node (ref "OLED1") (pin "24") (pinfunction "D6_24") (pintype "passive+no_connect"))
    )
    (net (code "204") (name "unconnected-(OLED1-D7-Pad25)") (class "Default")
      (node (ref "OLED1") (pin "25") (pinfunction "D7_25") (pintype "passive+no_connect"))
    )
    (net (code "205") (name "unconnected-(OLED1-DC{slash}I2C_SA0-Pad15)") (class "Default")
      (node (ref "OLED1") (pin "15") (pinfunction "DC/I2C_SA0_15") (pintype "passive+no_connect"))
    )
    (net (code "206") (name "unconnected-(OLED1-E{slash}RD-Pad17)") (class "Default")
      (node (ref "OLED1") (pin "17") (pinfunction "E/RD_17") (pintype "passive+no_connect"))
    )
    (net (code "207") (name "unconnected-(OLED1-NC-Pad7)") (class "Default")
      (node (ref "OLED1") (pin "7") (pinfunction "NC_7") (pintype "passive+no_connect"))
    )
    (net (code "208") (name "unconnected-(OLED1-R{slash}W-Pad16)") (class "Default")
      (node (ref "OLED1") (pin "16") (pinfunction "R/W_16") (pintype "passive+no_connect"))
    )
    (net (code "209") (name "unconnected-(OLED1-{slash}CS-Pad13)") (class "Default")
      (node (ref "OLED1") (pin "13") (pinfunction "/CS_13") (pintype "passive+no_connect"))
    )
    (net (code "210") (name "unconnected-(S3-Pad2)") (class "Default")
      (node (ref "S3") (pin "2") (pinfunction "2_2") (pintype "passive"))
    )
    (net (code "211") (name "unconnected-(S3-Pad4)") (class "Default")
      (node (ref "S3") (pin "4") (pinfunction "4_4") (pintype "passive"))
    )
    (net (code "212") (name "unconnected-(S4-Pad2)") (class "Default")
      (node (ref "S4") (pin "2") (pinfunction "2_2") (pintype "passive"))
    )
    (net (code "213") (name "unconnected-(S4-Pad4)") (class "Default")
      (node (ref "S4") (pin "4") (pinfunction "4_4") (pintype "passive"))
    )
    (net (code "214") (name "unconnected-(S5-Pad2)") (class "Default")
      (node (ref "S5") (pin "2") (pinfunction "2_2") (pintype "passive"))
    )
    (net (code "215") (name "unconnected-(S5-Pad4)") (class "Default")
      (node (ref "S5") (pin "4") (pinfunction "4_4") (pintype "passive"))
    )
    (net (code "216") (name "unconnected-(S8-Pad2)") (class "Default")
      (node (ref "S8") (pin "2") (pinfunction "2_2") (pintype "passive"))
    )
    (net (code "217") (name "unconnected-(S8-Pad4)") (class "Default")
      (node (ref "S8") (pin "4") (pinfunction "4_4") (pintype "passive"))
    )
    (net (code "218") (name "unconnected-(S9-Pad3)") (class "Default")
      (node (ref "S9") (pin "3") (pinfunction "3_3") (pintype "passive+no_connect"))
    )
    (net (code "219") (name "unconnected-(S9-Pad6)") (class "Default")
      (node (ref "S9") (pin "6") (pinfunction "6_6") (pintype "passive+no_connect"))
    )
    (net (code "220") (name "unconnected-(S10-Pad2)") (class "Default")
      (node (ref "S10") (pin "2") (pinfunction "2_2") (pintype "passive"))
    )
    (net (code "221") (name "unconnected-(S10-Pad4)") (class "Default")
      (node (ref "S10") (pin "4") (pinfunction "4_4") (pintype "passive"))
    )
    (net (code "222") (name "unconnected-(S11-Pad2)") (class "Default")
      (node (ref "S11") (pin "2") (pinfunction "2_2") (pintype "passive"))
    )
    (net (code "223") (name "unconnected-(S11-Pad4)") (class "Default")
      (node (ref "S11") (pin "4") (pinfunction "4_4") (pintype "passive"))
    )
    (net (code "224") (name "unconnected-(S12-Pad2)") (class "Default")
      (node (ref "S12") (pin "2") (pinfunction "2_2") (pintype "passive"))
    )
    (net (code "225") (name "unconnected-(S12-Pad4)") (class "Default")
      (node (ref "S12") (pin "4") (pinfunction "4_4") (pintype "passive"))
    )
    (net (code "226") (name "unconnected-(S13-Pad2)") (class "Default")
      (node (ref "S13") (pin "2") (pinfunction "2_2") (pintype "passive"))
    )
    (net (code "227") (name "unconnected-(S13-Pad4)") (class "Default")
      (node (ref "S13") (pin "4") (pinfunction "4_4") (pintype "passive"))
    )
    (net (code "228") (name "unconnected-(S14-Pad2)") (class "Default")
      (node (ref "S14") (pin "2") (pinfunction "2_2") (pintype "passive"))
    )
    (net (code "229") (name "unconnected-(S14-Pad4)") (class "Default")
      (node (ref "S14") (pin "4") (pinfunction "4_4") (pintype "passive"))
    )
  )
)
